# STM32H730_PINOUT.net
KiCad netlist of a schematic drawn in Altium Designer
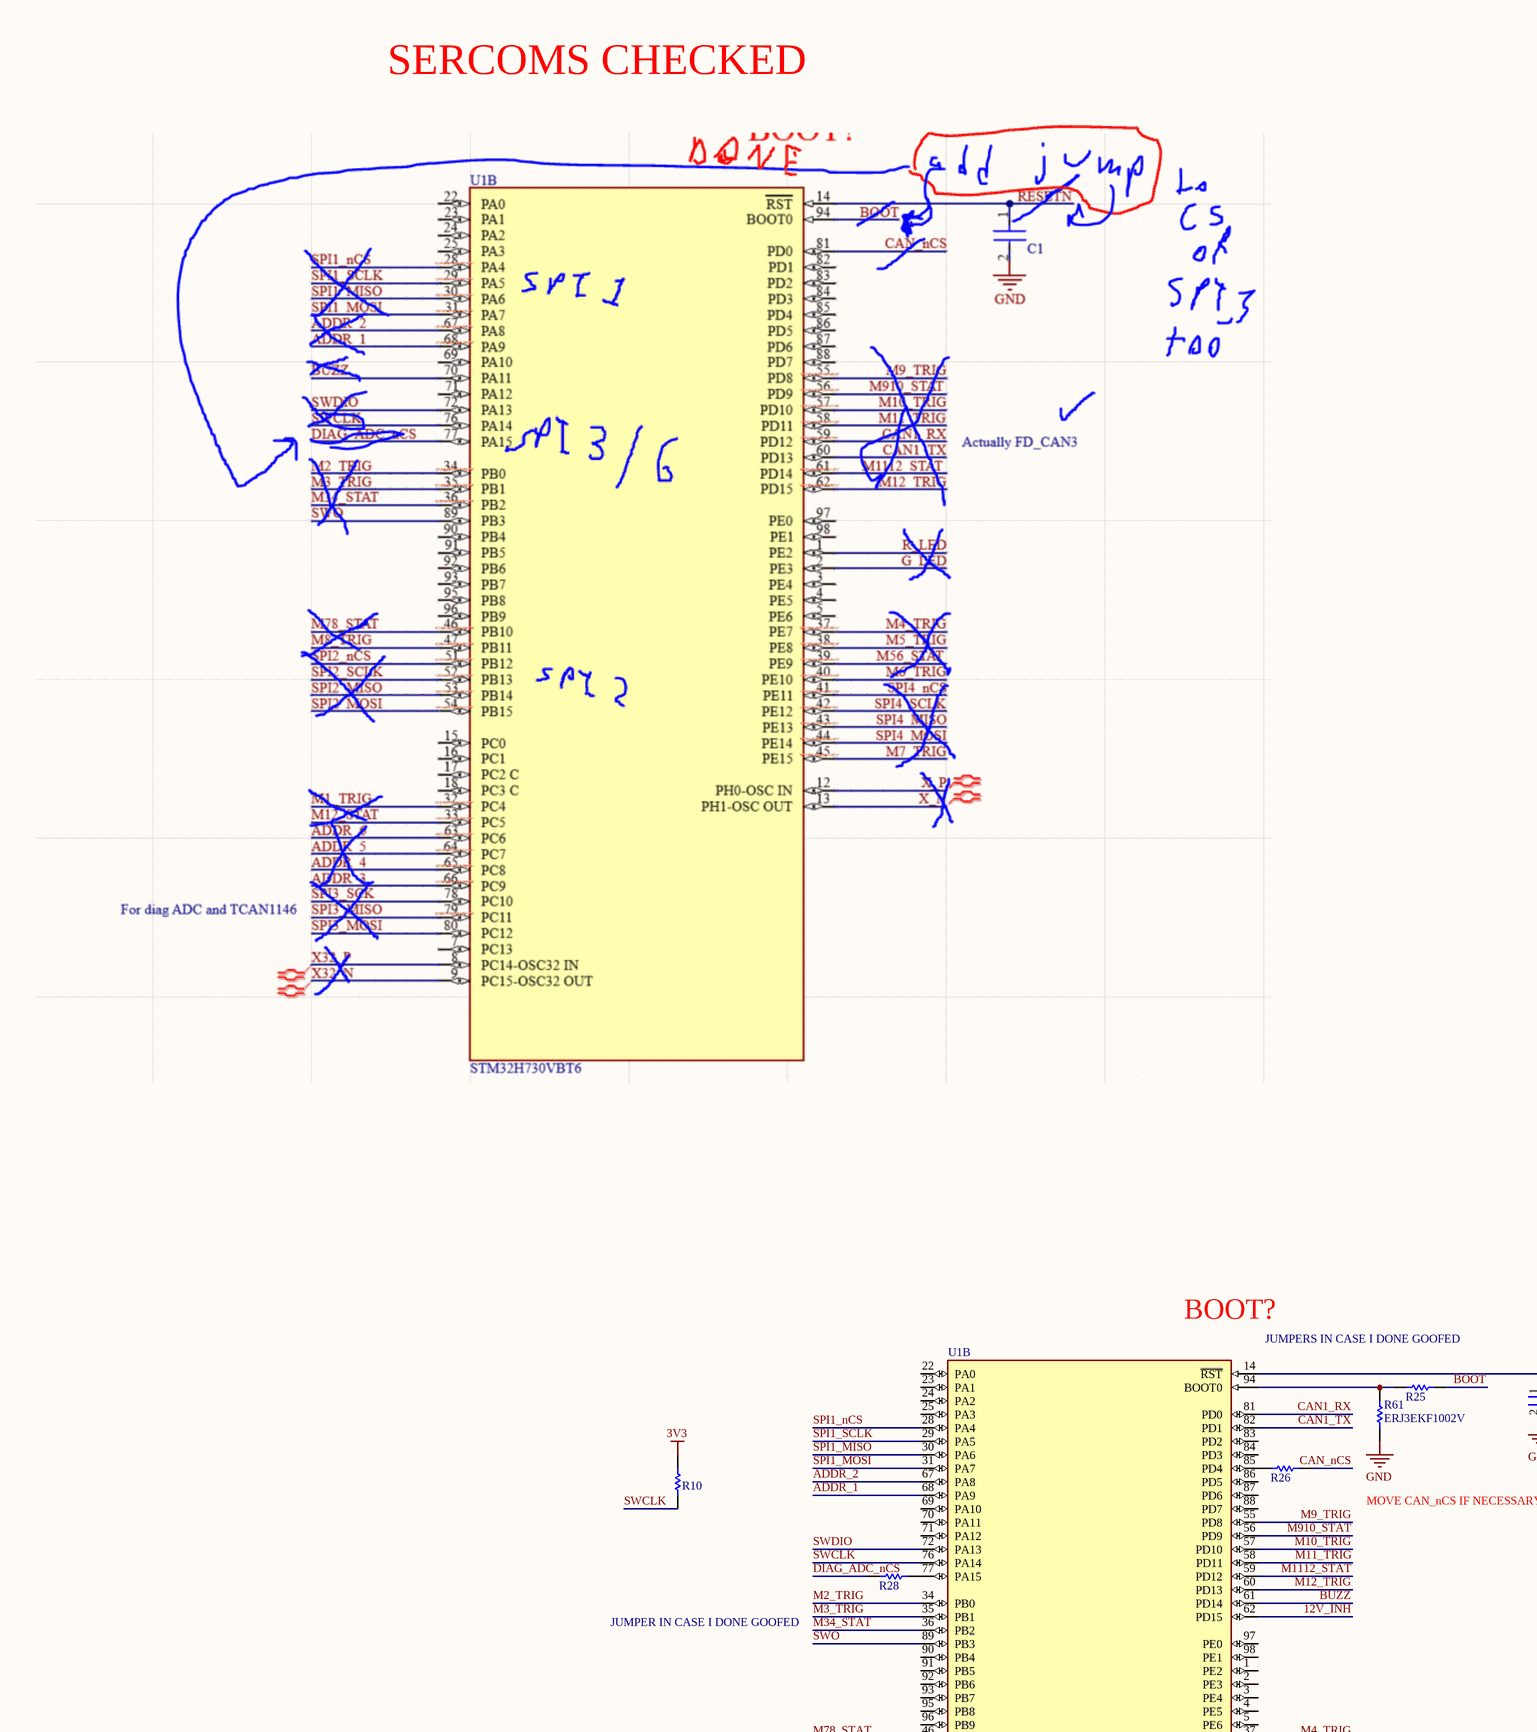
[diagram p0: STM32H730_PINOUT.SchDoc, top left]
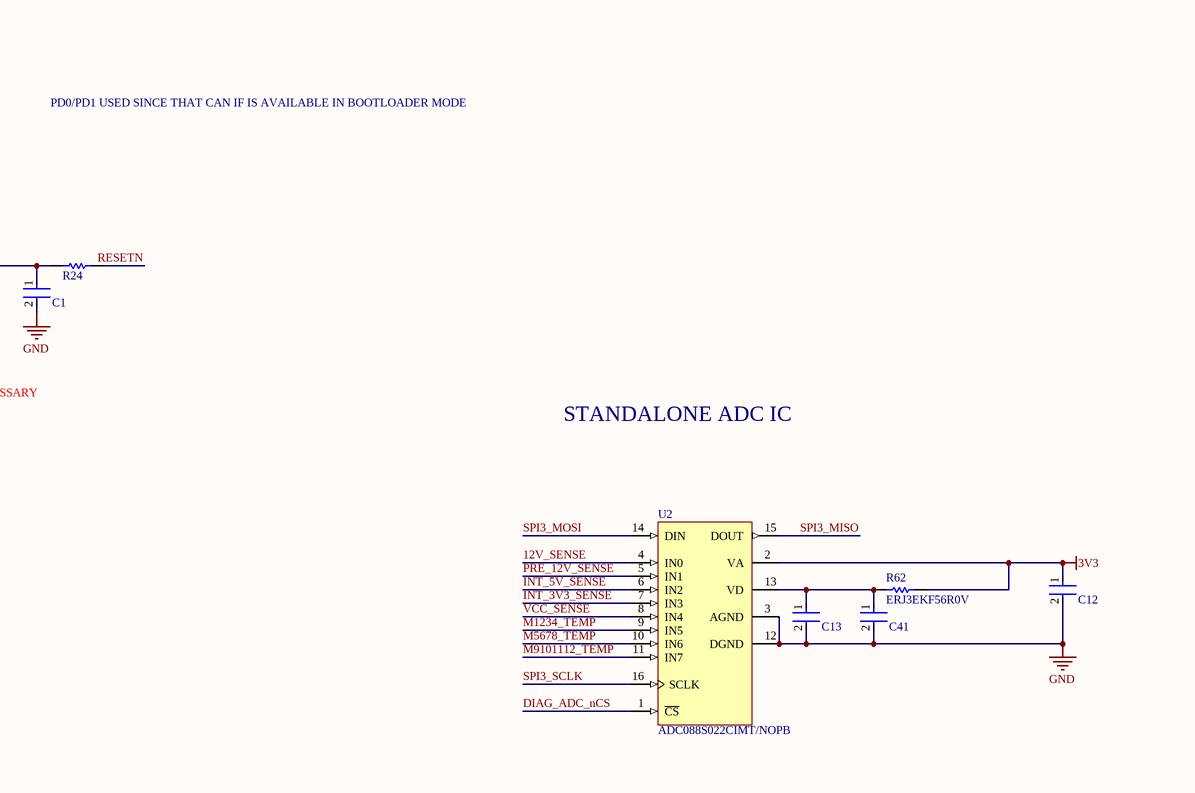
[diagram p1: STM32H730_PINOUT.SchDoc, top middle]
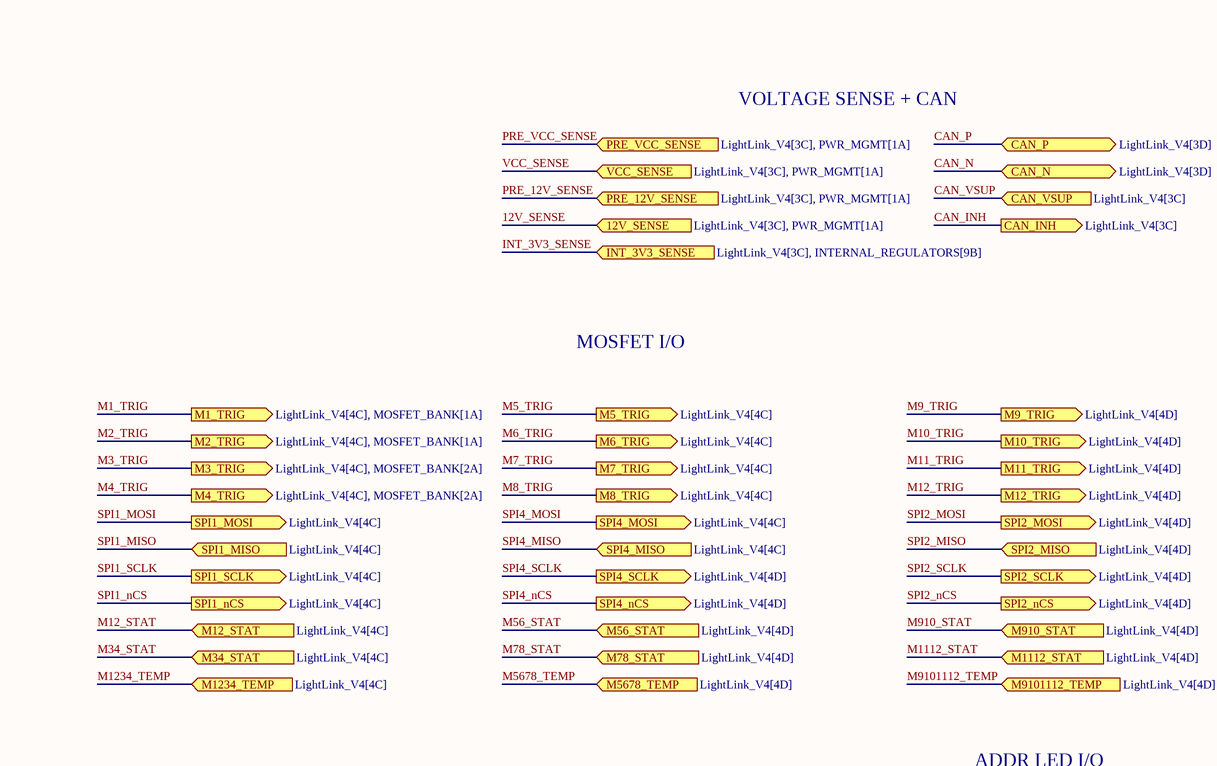
[diagram p2: STM32H730_PINOUT.SchDoc, top right]
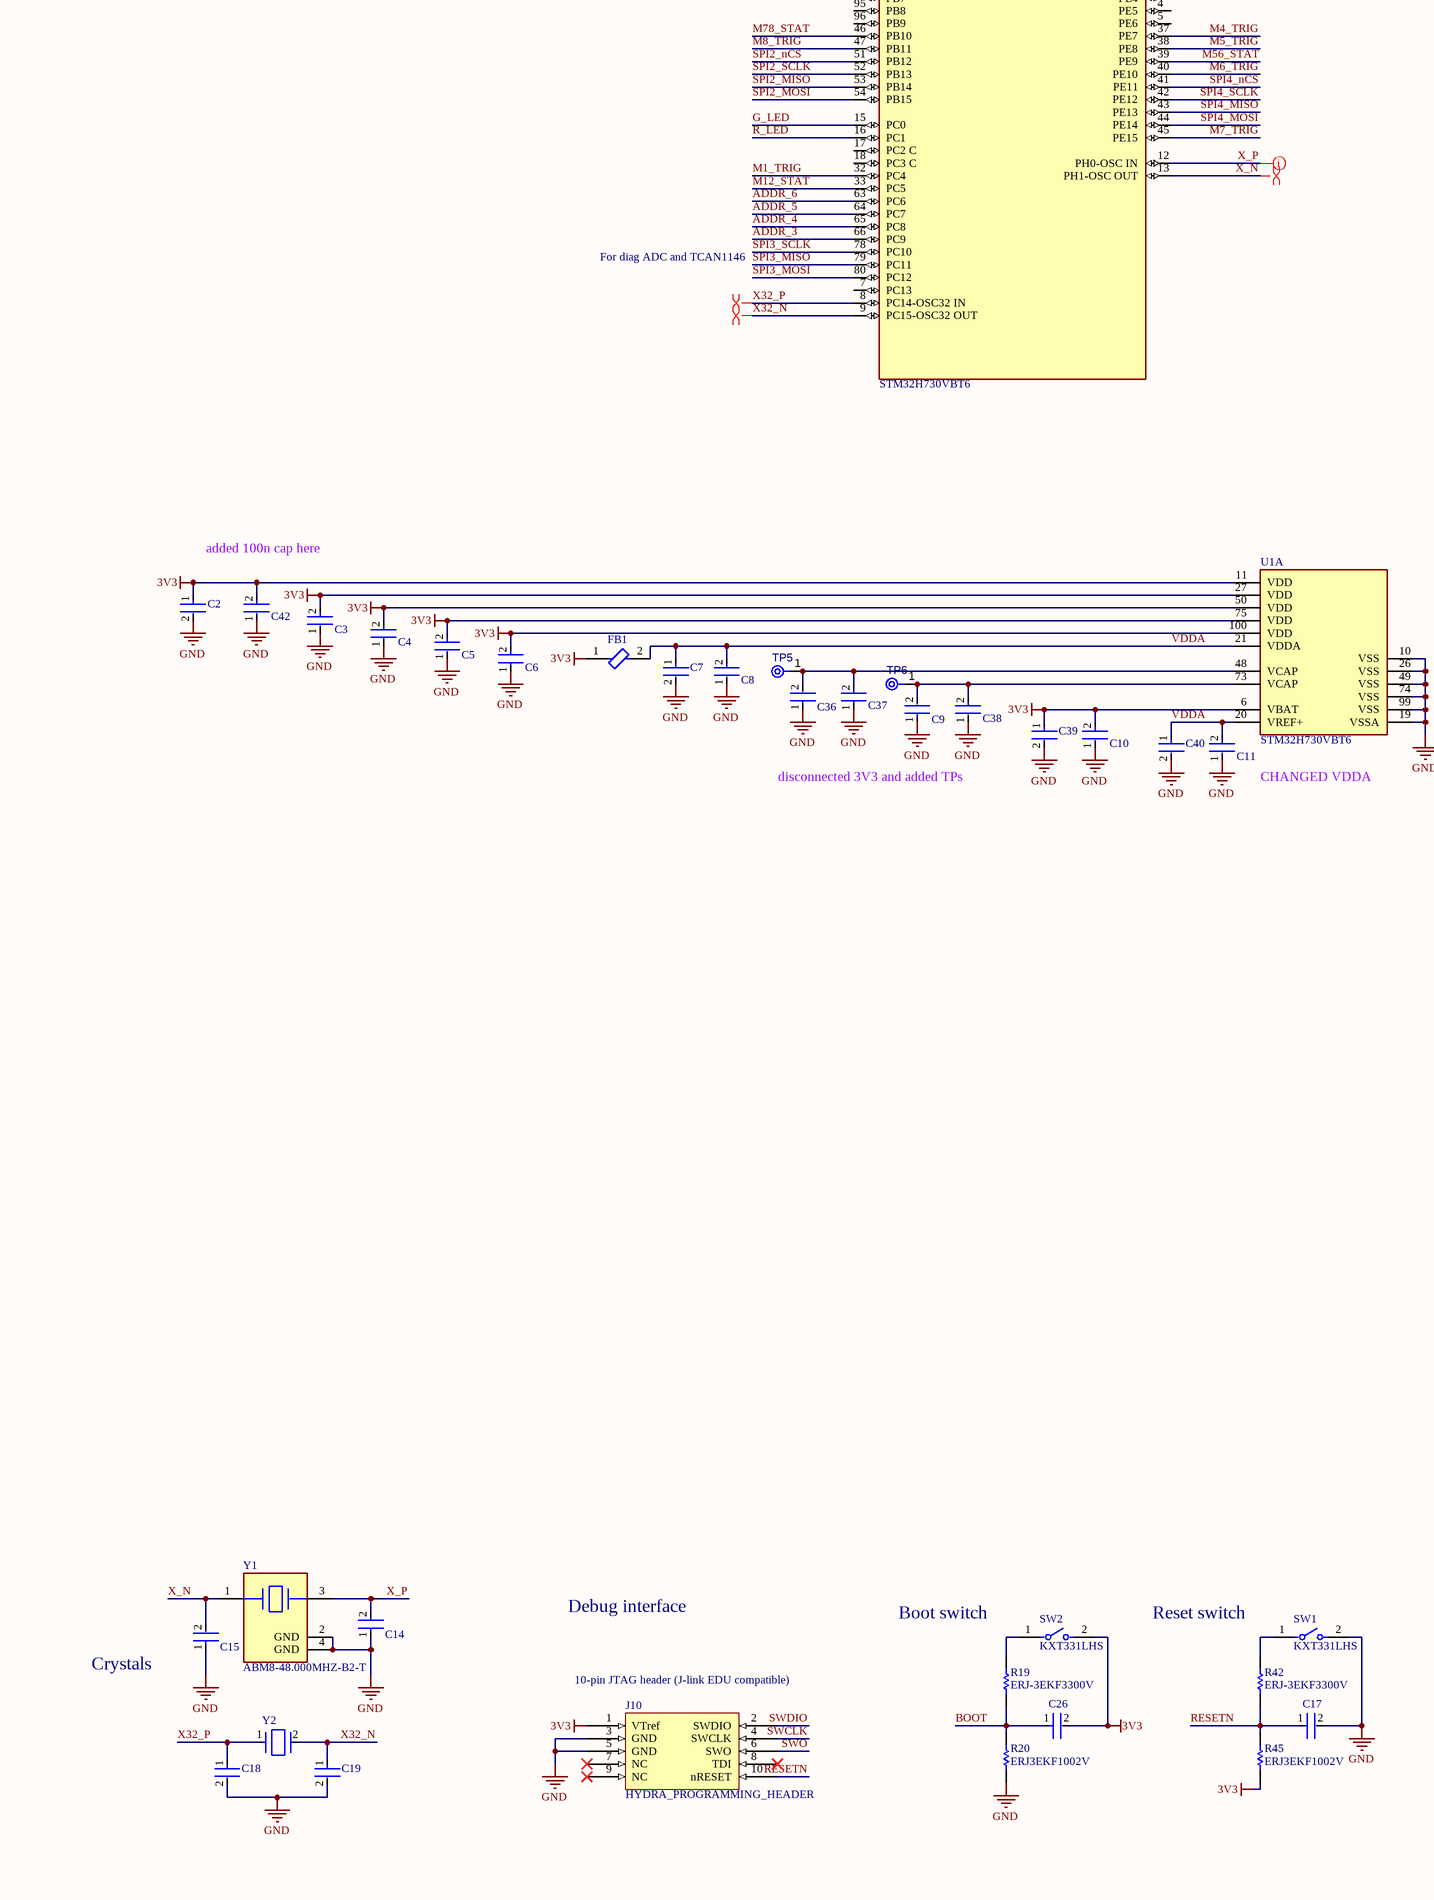
[diagram p3: STM32H730_PINOUT.SchDoc, bottom left]
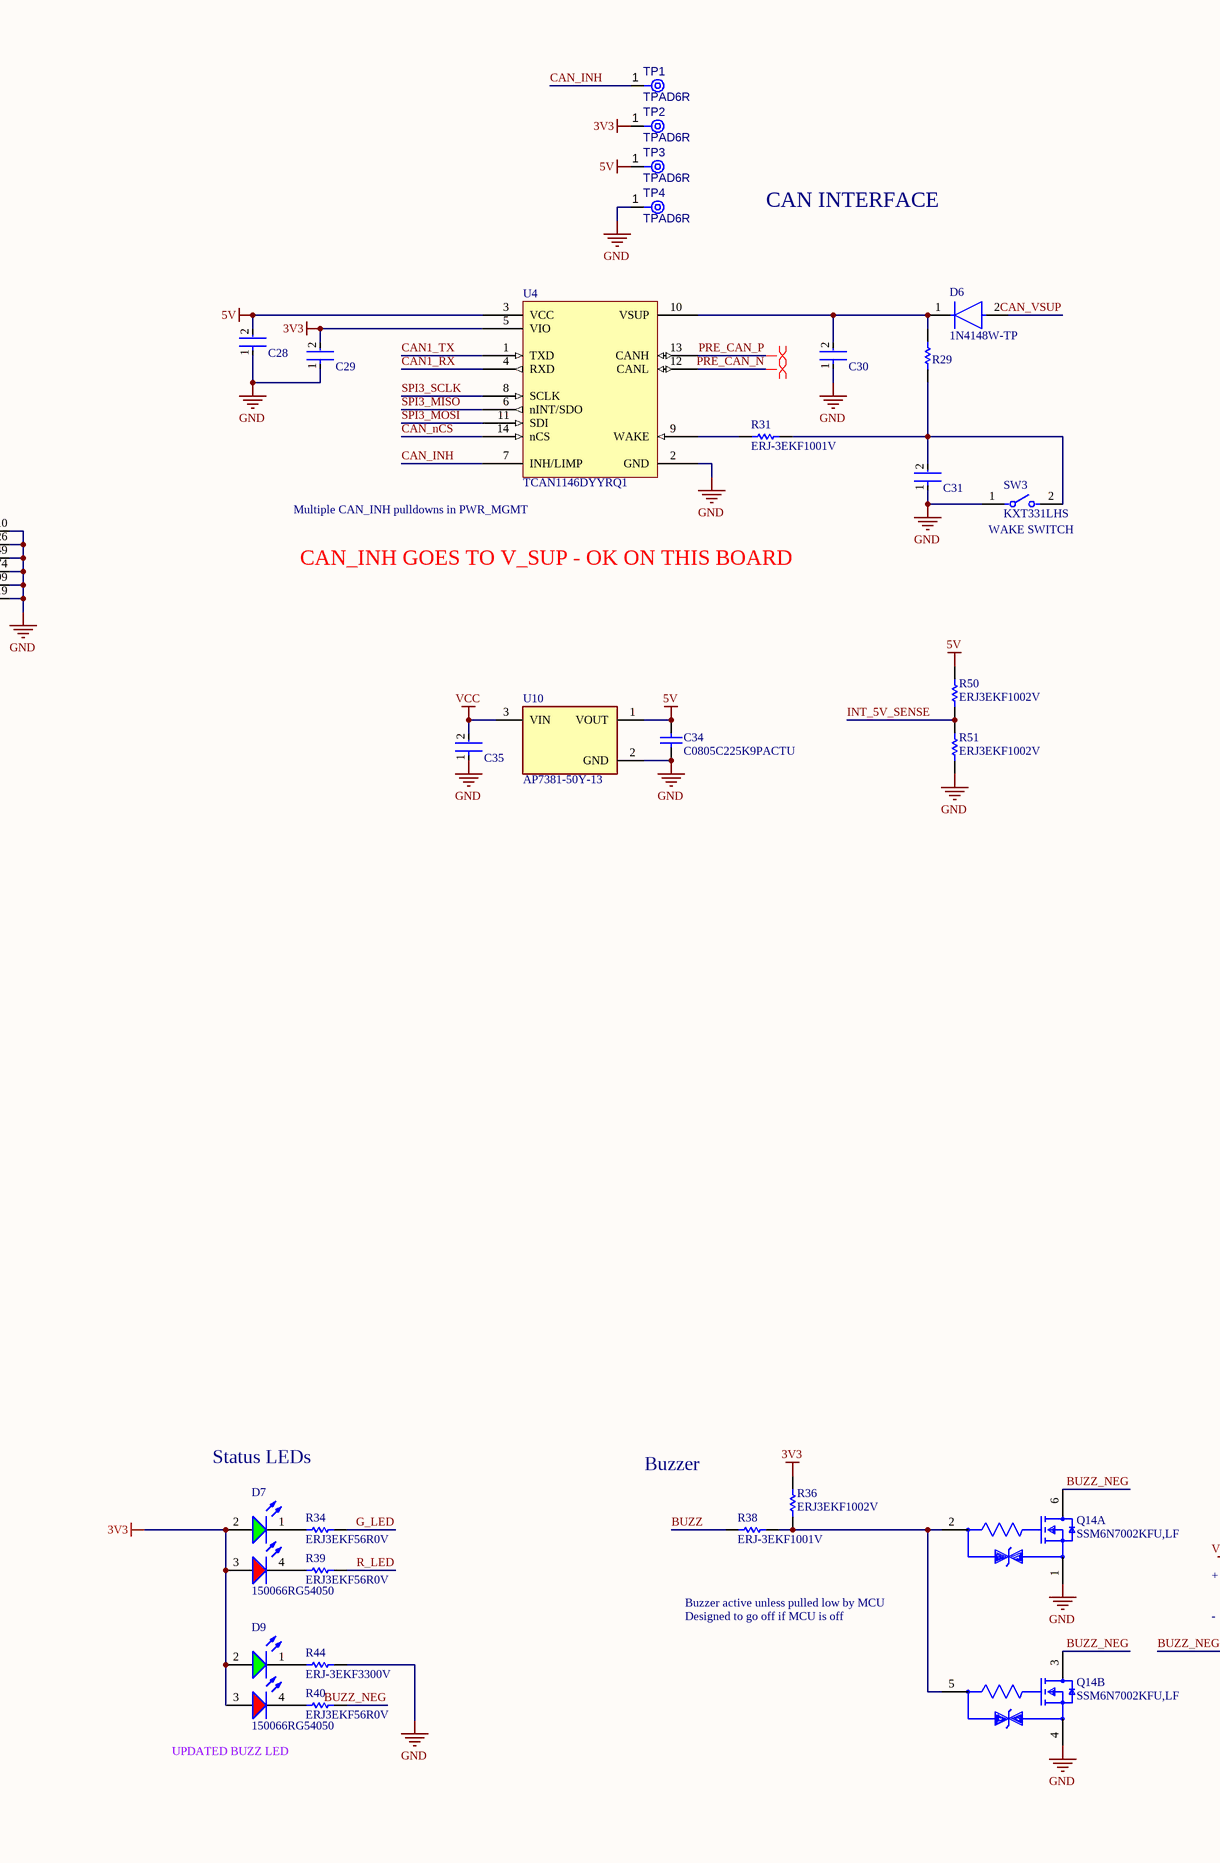
[diagram p4: STM32H730_PINOUT.SchDoc, bottom middle]
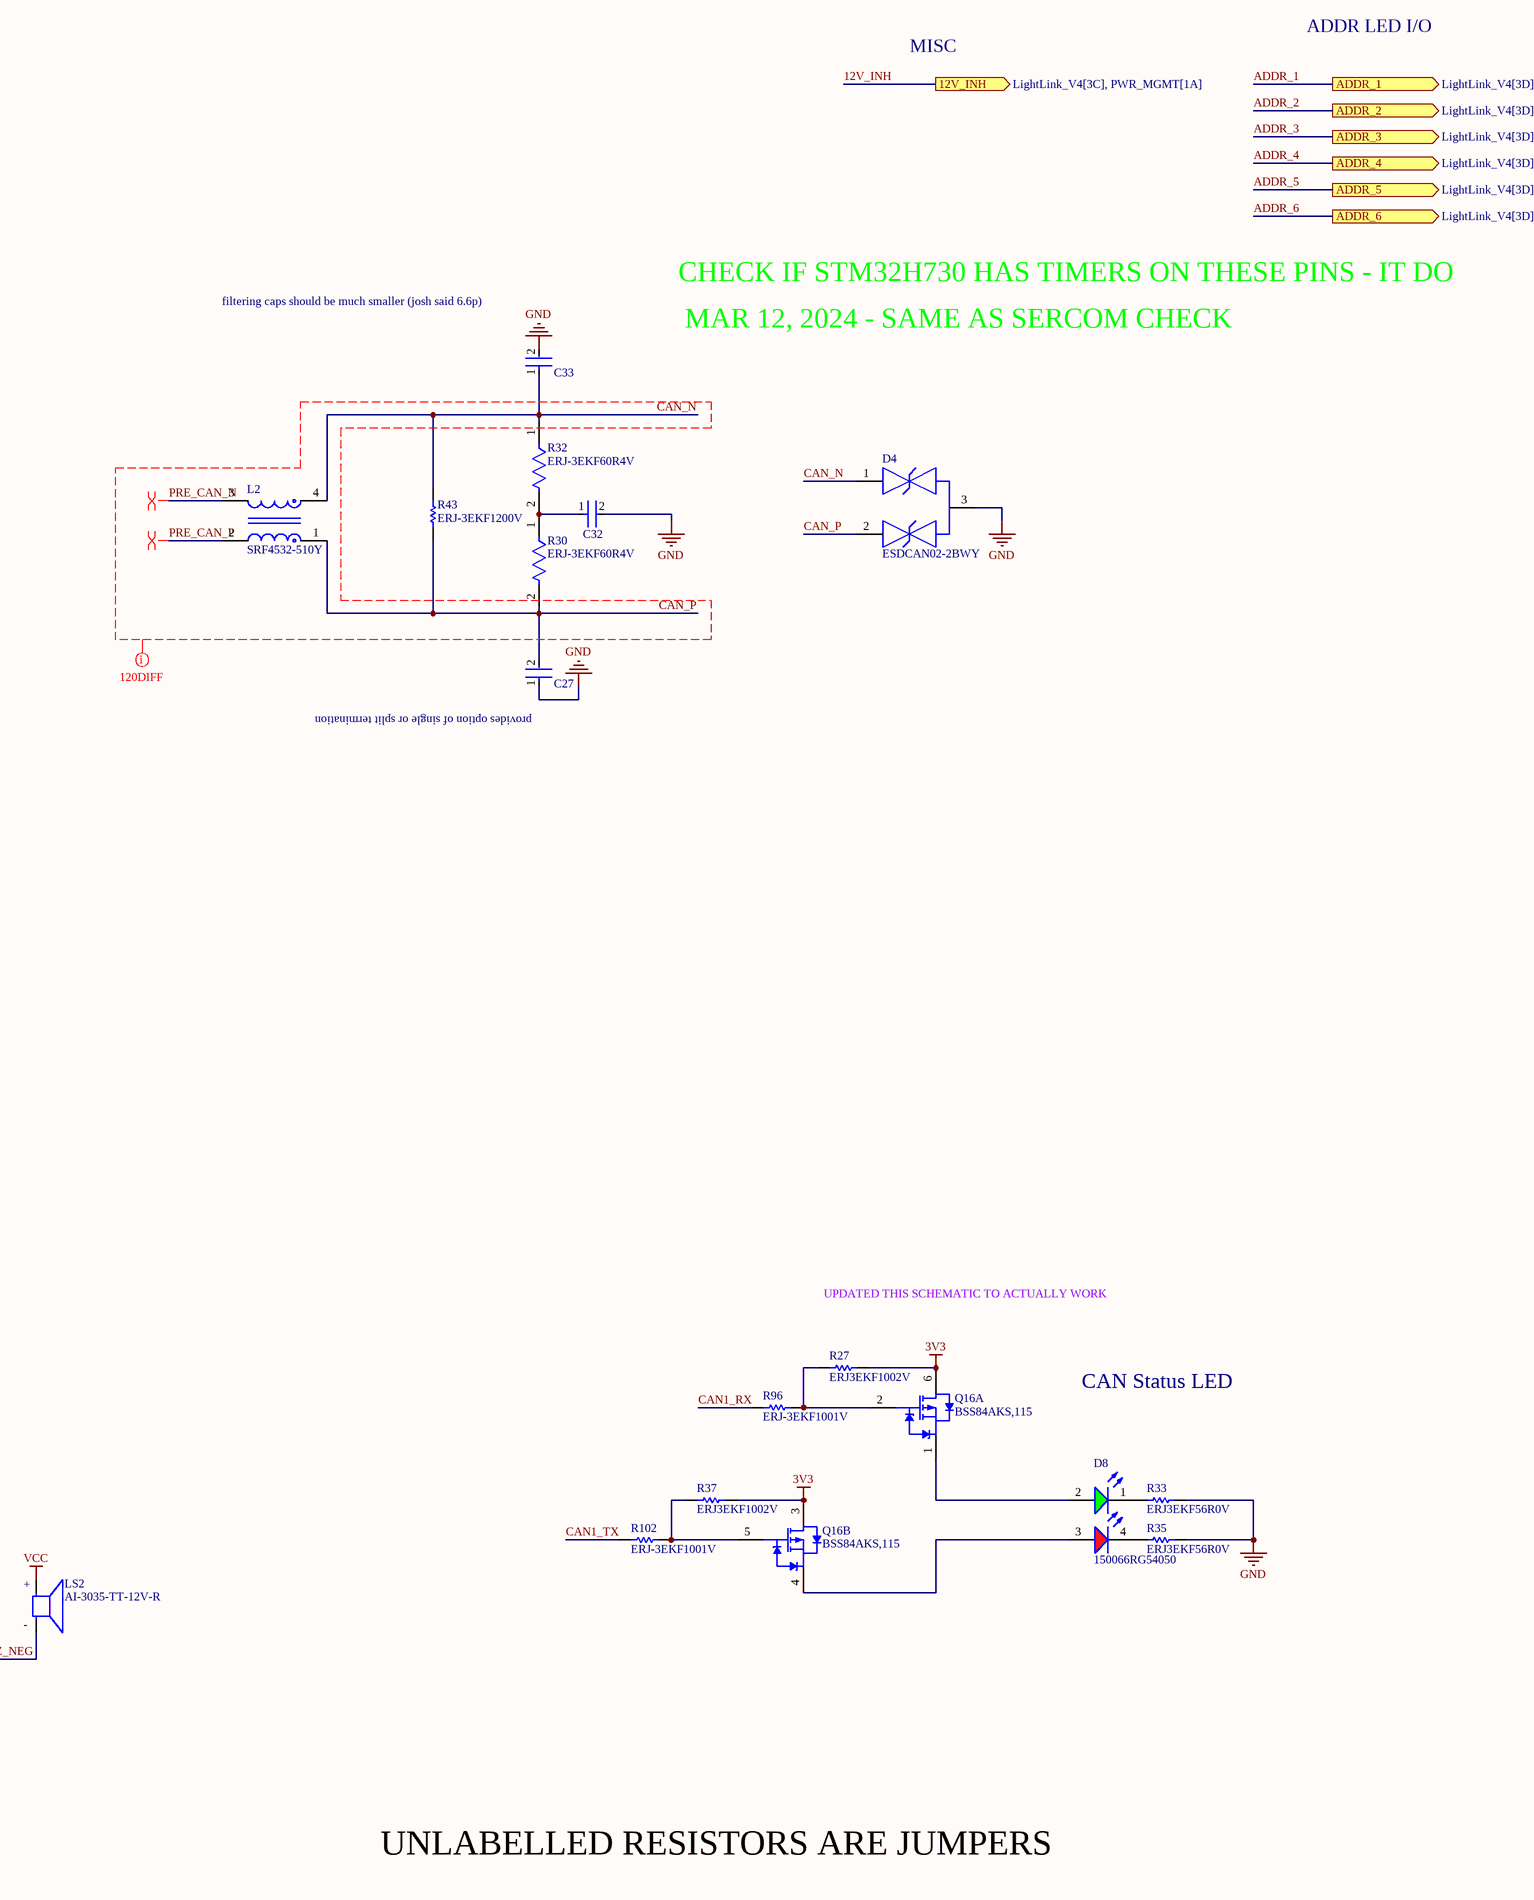
[diagram p5: STM32H730_PINOUT.SchDoc, bottom right]

(export (version "E")
  (design (tool "Eeschema 10.0.6"))
  (components
    (comp (ref "C1")
      (value "C0402C104K8PACTU")
      (footprint "FP-C0402-BB-MFG")
      (description "CAP CER 0.1UF 10V X5R 0402")
      (fields (field (name "MANUFACTURER") "Kemet") (field (name "TOLERANCE") "0.1"))
      (libsource (lib "Altium Content Vault") (part "b4654b650e69147ec39a6b967a45e02"))
    )
    (comp (ref "C2")
      (value "C1005X5R1A475K050BC")
      (footprint "FP-C1005-050-0_15-MFG")
      (description "CAP CER 4.7UF 10V X5R 0402")
      (fields (field (name "TOLERANCE") "10%"))
      (libsource (lib "Altium Content Vault") (part "b4654b650e69147ec39a6b967a45e02"))
    )
    (comp (ref "C3")
      (value "GRM155R71C104KA88D")
      (footprint "FP-GRM15-MFG")
      (description "CAP CER 0.1UF 16V X7R 0402")
      (fields
        (field (name "TOLERANCE") "10%")
        (field (name "OCTOPART") "https://octopart.com/grm155r71c104ka88d-murata-196880")
      )
      (libsource (lib "Altium Content Vault") (part "236180d848d6139a670b325ea6854c9"))
    )
    (comp (ref "C4")
      (value "GRM155R71C104KA88D")
      (footprint "FP-GRM15-MFG")
      (description "CAP CER 0.1UF 16V X7R 0402")
      (fields
        (field (name "TOLERANCE") "10%")
        (field (name "OCTOPART") "https://octopart.com/grm155r71c104ka88d-murata-196880")
      )
      (libsource (lib "Altium Content Vault") (part "236180d848d6139a670b325ea6854c9"))
    )
    (comp (ref "C5")
      (value "GRM155R71C104KA88D")
      (footprint "FP-GRM15-MFG")
      (description "CAP CER 0.1UF 16V X7R 0402")
      (fields
        (field (name "TOLERANCE") "10%")
        (field (name "OCTOPART") "https://octopart.com/grm155r71c104ka88d-murata-196880")
      )
      (libsource (lib "Altium Content Vault") (part "236180d848d6139a670b325ea6854c9"))
    )
    (comp (ref "C6")
      (value "GRM155R71C104KA88D")
      (footprint "FP-GRM15-MFG")
      (description "CAP CER 0.1UF 16V X7R 0402")
      (fields
        (field (name "TOLERANCE") "10%")
        (field (name "OCTOPART") "https://octopart.com/grm155r71c104ka88d-murata-196880")
      )
      (libsource (lib "Altium Content Vault") (part "236180d848d6139a670b325ea6854c9"))
    )
    (comp (ref "C7")
      (value "EMK105BJ105KV-F")
      (footprint "FP-0402-L_1_0_0_05-W_0_5-IPC_A")
      (description "None")
      (fields (field (name "TOLERANCE") "10%"))
      (libsource (lib "Altium Content Vault") (part "b4654b650e69147ec39a6b967a45e02"))
    )
    (comp (ref "C8")
      (value "GRM155R71C104KA88D")
      (footprint "FP-GRM15-MFG")
      (description "CAP CER 0.1UF 16V X7R 0402")
      (fields
        (field (name "TOLERANCE") "10%")
        (field (name "OCTOPART") "https://octopart.com/grm155r71c104ka88d-murata-196880")
      )
      (libsource (lib "Altium Content Vault") (part "236180d848d6139a670b325ea6854c9"))
    )
    (comp (ref "C9")
      (value "C1005X7S1A225K050BC")
      (footprint "FP-C1005-050-0_15-0_1-MFG")
      (description "CAP CER 2.2UF 10V X7S 0402")
      (fields (field (name "TOLERANCE") "10%"))
      (libsource (lib "Altium Content Vault") (part "b4654b650e69147ec39a6b967a45e02"))
    )
    (comp (ref "C10")
      (value "GRM155R71C104KA88D")
      (footprint "FP-GRM15-MFG")
      (description "CAP CER 0.1UF 16V X7R 0402")
      (fields
        (field (name "TOLERANCE") "10%")
        (field (name "OCTOPART") "https://octopart.com/grm155r71c104ka88d-murata-196880")
      )
      (libsource (lib "Altium Content Vault") (part "236180d848d6139a670b325ea6854c9"))
    )
    (comp (ref "C11")
      (value "GRM155R71C104KA88D")
      (footprint "FP-GRM15-MFG")
      (description "CAP CER 0.1UF 16V X7R 0402")
      (fields
        (field (name "TOLERANCE") "10%")
        (field (name "OCTOPART") "https://octopart.com/grm155r71c104ka88d-murata-196880")
      )
      (libsource (lib "Altium Content Vault") (part "236180d848d6139a670b325ea6854c9"))
    )
    (comp (ref "C12")
      (value "C0402C104K8PACTU")
      (footprint "FP-C0402-BB-MFG")
      (description "CAP CER 0.1UF 10V X5R 0402")
      (fields (field (name "MANUFACTURER") "Kemet") (field (name "TOLERANCE") "0.1"))
      (libsource (lib "Altium Content Vault") (part "b4654b650e69147ec39a6b967a45e02"))
    )
    (comp (ref "C13")
      (value "C0402C104K8PACTU")
      (footprint "FP-C0402-BB-MFG")
      (description "CAP CER 0.1UF 10V X5R 0402")
      (fields (field (name "MANUFACTURER") "Kemet") (field (name "TOLERANCE") "0.1"))
      (libsource (lib "Altium Content Vault") (part "b4654b650e69147ec39a6b967a45e02"))
    )
    (comp (ref "C14")
      (value "08051A6R8CAT2A")
      (footprint "FP-0805-L_2_01_0_2-W_1_25-MFG")
      (description "General Purpose Ceramic Capacitor, 0805, 6.8pF, 0.25pF, C0G, 30ppm/°C, 100V")
      (fields (field (name "VOLTAGE") "100V") (field (name "TOLERANCE") "5%"))
      (libsource (lib "Altium Content Vault") (part "02cd4be3c70576c341d710602a673aa"))
    )
    (comp (ref "C15")
      (value "08051A6R8CAT2A")
      (footprint "FP-0805-L_2_01_0_2-W_1_25-MFG")
      (description "General Purpose Ceramic Capacitor, 0805, 6.8pF, 0.25pF, C0G, 30ppm/°C, 100V")
      (fields (field (name "VOLTAGE") "100V") (field (name "TOLERANCE") "5%"))
      (libsource (lib "Altium Content Vault") (part "02cd4be3c70576c341d710602a673aa"))
    )
    (comp (ref "C17")
      (value "C0402C104K8PACTU")
      (footprint "FP-C0402-BB-MFG")
      (description "CAP CER 0.1UF 10V X5R 0402")
      (fields (field (name "MANUFACTURER") "Kemet") (field (name "TOLERANCE") "0.1"))
      (libsource (lib "Altium Content Vault") (part "b4654b650e69147ec39a6b967a45e02"))
    )
    (comp (ref "C18")
      (value "C0805C180J5GACTU")
      (footprint "FP-C0805C-DN-MFG")
      (description "CAP CER 18PF 50V C0G/NP0 0805")
      (fields
        (field (name "OCTOPART") "https://octopart.com/c0805c180j5gactu-kemet-144810")
        (field (name "TOLERANCE") "0.05")
      )
      (libsource (lib "Altium Content Vault") (part "b4654b650e69147ec39a6b967a45e02"))
    )
    (comp (ref "C19")
      (value "C0805C180J5GACTU")
      (footprint "FP-C0805C-DN-MFG")
      (description "CAP CER 18PF 50V C0G/NP0 0805")
      (fields
        (field (name "OCTOPART") "https://octopart.com/c0805c180j5gactu-kemet-144810")
        (field (name "TOLERANCE") "0.05")
      )
      (libsource (lib "Altium Content Vault") (part "b4654b650e69147ec39a6b967a45e02"))
    )
    (comp (ref "C26")
      (value "C0402C104K8PACTU")
      (footprint "FP-C0402-BB-MFG")
      (description "CAP CER 0.1UF 10V X5R 0402")
      (fields (field (name "MANUFACTURER") "Kemet") (field (name "TOLERANCE") "0.1"))
      (libsource (lib "Altium Content Vault") (part "b4654b650e69147ec39a6b967a45e02"))
    )
    (comp (ref "C27")
      (value "C0402C104K8PACTU")
      (footprint "FP-C0402-BB-MFG")
      (description "CAP CER 0.1UF 10V X5R 0402")
      (fields (field (name "MANUFACTURER") "Kemet") (field (name "TOLERANCE") "0.1"))
      (libsource (lib "Altium Content Vault") (part "b4654b650e69147ec39a6b967a45e02"))
    )
    (comp (ref "C28")
      (value "C0402C104K8PACTU")
      (footprint "FP-C0402-BB-MFG")
      (description "CAP CER 0.1UF 10V X5R 0402")
      (fields (field (name "MANUFACTURER") "Kemet") (field (name "TOLERANCE") "0.1"))
      (libsource (lib "Altium Content Vault") (part "b4654b650e69147ec39a6b967a45e02"))
    )
    (comp (ref "C29")
      (value "C0402C104K8PACTU")
      (footprint "FP-C0402-BB-MFG")
      (description "CAP CER 0.1UF 10V X5R 0402")
      (fields (field (name "MANUFACTURER") "Kemet") (field (name "TOLERANCE") "0.1"))
      (libsource (lib "Altium Content Vault") (part "b4654b650e69147ec39a6b967a45e02"))
    )
    (comp (ref "C30")
      (value "C0402C104K8PACTU")
      (footprint "FP-C0402-BB-MFG")
      (description "CAP CER 0.1UF 10V X5R 0402")
      (fields (field (name "MANUFACTURER") "Kemet") (field (name "TOLERANCE") "0.1"))
      (libsource (lib "Altium Content Vault") (part "b4654b650e69147ec39a6b967a45e02"))
    )
    (comp (ref "C31")
      (value "C0402C104K8PACTU")
      (footprint "FP-C0402-BB-MFG")
      (description "CAP CER 0.1UF 10V X5R 0402")
      (fields (field (name "MANUFACTURER") "Kemet") (field (name "TOLERANCE") "0.1"))
      (libsource (lib "Altium Content Vault") (part "b4654b650e69147ec39a6b967a45e02"))
    )
    (comp (ref "C32")
      (value "C0402C104K8PACTU")
      (footprint "FP-C0402-BB-MFG")
      (description "CAP CER 0.1UF 10V X5R 0402")
      (fields (field (name "MANUFACTURER") "Kemet") (field (name "TOLERANCE") "0.1"))
      (libsource (lib "Altium Content Vault") (part "b4654b650e69147ec39a6b967a45e02"))
    )
    (comp (ref "C33")
      (value "C0402C104K8PACTU")
      (footprint "FP-C0402-BB-MFG")
      (description "CAP CER 0.1UF 10V X5R 0402")
      (fields (field (name "MANUFACTURER") "Kemet") (field (name "TOLERANCE") "0.1"))
      (libsource (lib "Altium Content Vault") (part "b4654b650e69147ec39a6b967a45e02"))
    )
    (comp (ref "C34")
      (value "C0805C225K9PACTU")
      (footprint "CAPC2013X145X50ML20T25")
      (fields (field (name "MANUFACTURER") "Kemet"))
      (libsource (lib "Altium Content Vault") (part "CAP"))
    )
    (comp (ref "C35")
      (value "C0402C104K8PACTU")
      (footprint "FP-C0402-BB-MFG")
      (description "CAP CER 0.1UF 10V X5R 0402")
      (fields (field (name "MANUFACTURER") "Kemet") (field (name "TOLERANCE") "0.1"))
      (libsource (lib "Altium Content Vault") (part "b4654b650e69147ec39a6b967a45e02"))
    )
    (comp (ref "C36")
      (value "C1005X7S1A225K050BC")
      (footprint "FP-C1005-050-0_15-0_1-MFG")
      (description "CAP CER 2.2UF 10V X7S 0402")
      (fields (field (name "TOLERANCE") "10%"))
      (libsource (lib "Altium Content Vault") (part "b4654b650e69147ec39a6b967a45e02"))
    )
    (comp (ref "C37")
      (value "GRM155R71C104KA88D")
      (footprint "FP-GRM15-MFG")
      (description "CAP CER 0.1UF 16V X7R 0402")
      (fields
        (field (name "TOLERANCE") "10%")
        (field (name "OCTOPART") "https://octopart.com/grm155r71c104ka88d-murata-196880")
      )
      (libsource (lib "Altium Content Vault") (part "236180d848d6139a670b325ea6854c9"))
    )
    (comp (ref "C38")
      (value "GRM155R71C104KA88D")
      (footprint "FP-GRM15-MFG")
      (description "CAP CER 0.1UF 16V X7R 0402")
      (fields
        (field (name "TOLERANCE") "10%")
        (field (name "OCTOPART") "https://octopart.com/grm155r71c104ka88d-murata-196880")
      )
      (libsource (lib "Altium Content Vault") (part "236180d848d6139a670b325ea6854c9"))
    )
    (comp (ref "C39")
      (value "EMK105BJ105KV-F")
      (footprint "FP-0402-L_1_0_0_05-W_0_5-IPC_A")
      (description "None")
      (fields (field (name "TOLERANCE") "10%"))
      (libsource (lib "Altium Content Vault") (part "b4654b650e69147ec39a6b967a45e02"))
    )
    (comp (ref "C40")
      (value "EMK105BJ105KV-F")
      (footprint "FP-0402-L_1_0_0_05-W_0_5-IPC_A")
      (description "None")
      (fields (field (name "TOLERANCE") "10%"))
      (libsource (lib "Altium Content Vault") (part "b4654b650e69147ec39a6b967a45e02"))
    )
    (comp (ref "C41")
      (value "C0402C104K8PACTU")
      (footprint "FP-C0402-BB-MFG")
      (description "CAP CER 0.1UF 10V X5R 0402")
      (fields (field (name "MANUFACTURER") "Kemet") (field (name "TOLERANCE") "0.1"))
      (libsource (lib "Altium Content Vault") (part "b4654b650e69147ec39a6b967a45e02"))
    )
    (comp (ref "C42")
      (value "GRM155R71C104KA88D")
      (footprint "FP-GRM15-MFG")
      (description "CAP CER 0.1UF 16V X7R 0402")
      (fields
        (field (name "TOLERANCE") "10%")
        (field (name "OCTOPART") "https://octopart.com/grm155r71c104ka88d-murata-196880")
      )
      (libsource (lib "Altium Content Vault") (part "236180d848d6139a670b325ea6854c9"))
    )
    (comp (ref "D4")
      (value "ESDCAN02-2BWY")
      (footprint "FP-SOT323-3L-MFG")
      (description "TVS DIODE 26.5V 44V SOT323-3")
      (fields
        (field (name "MANUFACTURER") "STMicroelectronics")
        (field (name "OCTOPART") "https://octopart.com/esdcan02-2bwy-stmicroelectronics-58631133")
      )
      (libsource (lib "Altium Content Vault") (part "0b9019fb5e52ed66df21ec1535be59d"))
    )
    (comp (ref "D6")
      (value "1N4148W-TP")
      (footprint "FP-SOD-123-IPC_A")
      (description "DIODE GEN PURP 100V 150MA SOD123")
      (libsource (lib "Altium Content Vault") (part "d7152d700b627762746794eb795d46e"))
    )
    (comp (ref "D7")
      (value "150066RG54050")
      (footprint "WL-SBCD_0606")
      (description "Led, Red/Grn, 180Mcd/230Mcd, 624Nm/525Nm Rohs Compliant: Yes")
      (libsource (lib "uORocketry Hardware") (part "WL-SBCD_0606_Red & Green"))
    )
    (comp (ref "D8")
      (value "150066RG54050")
      (footprint "WL-SBCD_0606")
      (description "Led, Red/Grn, 180Mcd/230Mcd, 624Nm/525Nm Rohs Compliant: Yes")
      (libsource (lib "uORocketry Hardware") (part "WL-SBCD_0606_Red & Green"))
    )
    (comp (ref "D9")
      (value "150066RG54050")
      (footprint "WL-SBCD_0606")
      (description "Led, Red/Grn, 180Mcd/230Mcd, 624Nm/525Nm Rohs Compliant: Yes")
      (libsource (lib "uORocketry Hardware") (part "WL-SBCD_0606_Red & Green"))
    )
    (comp (ref "FB1")
      (value "BLM15PX601SN1D")
      (footprint "FP-BLM15-0_05-MFG")
      (description "Chip Ferrite Bead, 0402, 600Ω @ 100MHz, 0.23Ω, 25%, 900mA")
      (fields (field (name "TOLERANCE") "25%"))
      (libsource (lib "Altium Content Vault") (part "5f30dd21d616792df468990f7003faa"))
    )
    (comp (ref "J10")
      (value "HYDRA_PROGRAMMING_HEADER")
      (footprint "3220-10-0300-00-Footprint-1")
      (description "CONN HEADER SMD 10POS 1.27MM (specifically compatible with J-Link EDU cable) PN: 3220-10-0300-00")
      (libsource (lib "uORocketry Hardware") (part "3220-10-0300-00-Symbol-1"))
    )
    (comp (ref "L2")
      (value "SRF4532-510Y")
      (footprint "FP-SRF4532-MFG")
      (description "CMC 51UH 200MA 2LN 2KOHM SMD")
      (fields (field (name "TOLERANCE") "50%"))
      (libsource (lib "Altium Content Vault") (part "aca3f6a10b859f211cca95010157f3b"))
    )
    (comp (ref "LS2")
      (value "AI-3035-TT-12V-R")
      (footprint "AI-3035-TT-12V-R-Footprint-1")
      (description "Audio Indicator 12V 12mA 110dBA 3.5KHz Resonant Frequency Thru-Hole")
      (libsource (lib "uORocketry Hardware") (part "AI-3035-TT-12V-R"))
    )
    (comp (ref "Q14")
      (value "SSM6N7002KFU,LF")
      (footprint "FP-SSOP6-P-0_65A-MFG")
      (description "MOSFET 2N-CH 60V 0.3A")
      (libsource (lib "Altium Content Vault") (part "088aa6ac103fdeebe0d1c52ece6b7b9"))
    )
    (comp (ref "Q16")
      (value "BSS84AKS,115")
      (footprint "NXP-SOT363_L")
      (description "Dual P-Channel Trench MOSFET, -50 V, -0.16 A, -55 to 150 degC, 6-Pin SOT363, Tape and Reel")
      (fields (field (name "MANUFACTURER") "NXP Semiconductors"))
      (libsource (lib "Altium Content Vault") (part "NXP-PPMOS-SGDSGD-6_A"))
    )
    (comp (ref "R10")
      (value "ERJ3EKF1002V")
      (footprint "RESC1609X55X30LL15T15")
      (description "Chip Resistor, 10 KOhm, +/- 1%, 0.1 W, -55 to 155 degC, 0603 (1608 Metric), RoHS, Tape and Reel")
      (fields (field (name "TOLERANCE") "1%") (field (name "MANUFACTURER") "Panasonic"))
      (libsource (lib "Altium Content Vault") (part "RES-2"))
    )
    (comp (ref "R19")
      (value "ERJ-3EKF3300V")
      (footprint "RESC1608X55X30LL15T15")
      (description "Chip Resistor, 330 Ohm, +/- 1%, 0.1 W, -55 to 155 degC, 0603 (1608 Metric), RoHS, Tape and Reel")
      (libsource (lib "Altium Content Vault") (part "RES-2"))
    )
    (comp (ref "R20")
      (value "ERJ3EKF1002V")
      (footprint "RESC1609X55X30LL15T15")
      (description "Chip Resistor, 10 KOhm, +/- 1%, 0.1 W, -55 to 155 degC, 0603 (1608 Metric), RoHS, Tape and Reel")
      (fields (field (name "TOLERANCE") "1%") (field (name "MANUFACTURER") "Panasonic"))
      (libsource (lib "Altium Content Vault") (part "RES-2"))
    )
    (comp (ref "R24")
      (value "0402 JUMPER 0 OHM")
      (footprint "RESC1005X40X25NL05T05")
      (description "READ THE NAME")
      (libsource (lib "uORocketry Hardware") (part "RES"))
    )
    (comp (ref "R25")
      (value "0402 JUMPER 0 OHM")
      (footprint "RESC1005X40X25NL05T05")
      (description "READ THE NAME")
      (libsource (lib "uORocketry Hardware") (part "RES"))
    )
    (comp (ref "R26")
      (value "0402 JUMPER 0 OHM")
      (footprint "RESC1005X40X25NL05T05")
      (description "READ THE NAME")
      (libsource (lib "uORocketry Hardware") (part "RES"))
    )
    (comp (ref "R27")
      (value "ERJ3EKF1002V")
      (footprint "RESC1609X55X30LL15T15")
      (description "Chip Resistor, 10 KOhm, +/- 1%, 0.1 W, -55 to 155 degC, 0603 (1608 Metric), RoHS, Tape and Reel")
      (fields (field (name "TOLERANCE") "1%") (field (name "MANUFACTURER") "Panasonic"))
      (libsource (lib "Altium Content Vault") (part "RES-2"))
    )
    (comp (ref "R28")
      (value "0402 JUMPER 0 OHM")
      (footprint "RESC1005X40X25NL05T05")
      (description "READ THE NAME")
      (libsource (lib "uORocketry Hardware") (part "RES"))
    )
    (comp (ref "R29")
      (value "ERJ3EKF1002V")
      (footprint "RESC1609X55X30LL15T15")
      (description "Chip Resistor, 10 KOhm, +/- 1%, 0.1 W, -55 to 155 degC, 0603 (1608 Metric), RoHS, Tape and Reel")
      (fields (field (name "TOLERANCE") "1%") (field (name "MANUFACTURER") "Panasonic"))
      (libsource (lib "Altium Content Vault") (part "RES-2"))
    )
    (comp (ref "R30")
      (value "ERJ-3EKF60R4V")
      (footprint "FP-ERJ3EK-IPC_C")
      (description "RES SMD 60.4 OHM 1% 1/10W 0603")
      (fields (field (name "TOLERANCE") "1%"))
      (libsource (lib "Altium Content Vault") (part "1029c3af85768c4190bb7ad29bc67b5"))
    )
    (comp (ref "R31")
      (value "ERJ-3EKF1001V")
      (footprint "RESC1608X55X30LL15T15")
      (fields (field (name "MANUFACTURER") "Panasonic"))
      (libsource (lib "Altium Content Vault") (part "RES"))
    )
    (comp (ref "R32")
      (value "ERJ-3EKF60R4V")
      (footprint "FP-ERJ3EK-IPC_C")
      (description "RES SMD 60.4 OHM 1% 1/10W 0603")
      (fields (field (name "TOLERANCE") "1%"))
      (libsource (lib "Altium Content Vault") (part "1029c3af85768c4190bb7ad29bc67b5"))
    )
    (comp (ref "R33")
      (value "ERJ3EKF56R0V")
      (footprint "RESC1608X55X30NL15T15")
      (fields (field (name "MANUFACTURER") "Panasonic"))
      (libsource (lib "Altium Content Vault") (part "RES"))
    )
    (comp (ref "R34")
      (value "ERJ3EKF56R0V")
      (footprint "RESC1608X55X30NL15T15")
      (fields (field (name "MANUFACTURER") "Panasonic"))
      (libsource (lib "Altium Content Vault") (part "RES"))
    )
    (comp (ref "R35")
      (value "ERJ3EKF56R0V")
      (footprint "RESC1608X55X30NL15T15")
      (fields (field (name "MANUFACTURER") "Panasonic"))
      (libsource (lib "Altium Content Vault") (part "RES"))
    )
    (comp (ref "R36")
      (value "ERJ3EKF1002V")
      (footprint "RESC1609X55X30LL15T15")
      (description "Chip Resistor, 10 KOhm, +/- 1%, 0.1 W, -55 to 155 degC, 0603 (1608 Metric), RoHS, Tape and Reel")
      (fields (field (name "TOLERANCE") "1%") (field (name "MANUFACTURER") "Panasonic"))
      (libsource (lib "Altium Content Vault") (part "RES-2"))
    )
    (comp (ref "R37")
      (value "ERJ3EKF1002V")
      (footprint "RESC1609X55X30LL15T15")
      (description "Chip Resistor, 10 KOhm, +/- 1%, 0.1 W, -55 to 155 degC, 0603 (1608 Metric), RoHS, Tape and Reel")
      (fields (field (name "TOLERANCE") "1%") (field (name "MANUFACTURER") "Panasonic"))
      (libsource (lib "Altium Content Vault") (part "RES-2"))
    )
    (comp (ref "R38")
      (value "ERJ-3EKF1001V")
      (footprint "RESC1608X55X30LL15T15")
      (fields (field (name "MANUFACTURER") "Panasonic"))
      (libsource (lib "Altium Content Vault") (part "RES"))
    )
    (comp (ref "R39")
      (value "ERJ3EKF56R0V")
      (footprint "RESC1608X55X30NL15T15")
      (fields (field (name "MANUFACTURER") "Panasonic"))
      (libsource (lib "Altium Content Vault") (part "RES"))
    )
    (comp (ref "R40")
      (value "ERJ3EKF56R0V")
      (footprint "RESC1608X55X30NL15T15")
      (fields (field (name "MANUFACTURER") "Panasonic"))
      (libsource (lib "Altium Content Vault") (part "RES"))
    )
    (comp (ref "R42")
      (value "ERJ-3EKF3300V")
      (footprint "RESC1608X55X30LL15T15")
      (description "Chip Resistor, 330 Ohm, +/- 1%, 0.1 W, -55 to 155 degC, 0603 (1608 Metric), RoHS, Tape and Reel")
      (libsource (lib "Altium Content Vault") (part "RES-2"))
    )
    (comp (ref "R43")
      (value "ERJ-3EKF1200V")
      (footprint "RESC1609X55X30ML15T15")
      (description "Chip Resistor, 120 Ohm, +/- 1%, 0.1 W, -55 to 155 degC, 0603 (1608 Metric), RoHS, Tape and Reel")
      (fields (field (name "TOLERANCE") "1%") (field (name "MANUFACTURER") "Panasonic"))
      (libsource (lib "Altium Content Vault") (part "RES-2"))
    )
    (comp (ref "R44")
      (value "ERJ-3EKF3300V")
      (footprint "RESC1608X55X30LL15T15")
      (description "Chip Resistor, 330 Ohm, +/- 1%, 0.1 W, -55 to 155 degC, 0603 (1608 Metric), RoHS, Tape and Reel")
      (libsource (lib "Altium Content Vault") (part "RES-2"))
    )
    (comp (ref "R45")
      (value "ERJ3EKF1002V")
      (footprint "RESC1609X55X30LL15T15")
      (description "Chip Resistor, 10 KOhm, +/- 1%, 0.1 W, -55 to 155 degC, 0603 (1608 Metric), RoHS, Tape and Reel")
      (fields (field (name "TOLERANCE") "1%") (field (name "MANUFACTURER") "Panasonic"))
      (libsource (lib "Altium Content Vault") (part "RES-2"))
    )
    (comp (ref "R50")
      (value "ERJ3EKF1002V")
      (footprint "RESC1609X55X30LL15T15")
      (description "Chip Resistor, 10 KOhm, +/- 1%, 0.1 W, -55 to 155 degC, 0603 (1608 Metric), RoHS, Tape and Reel")
      (fields (field (name "TOLERANCE") "1%") (field (name "MANUFACTURER") "Panasonic"))
      (libsource (lib "Altium Content Vault") (part "RES-2"))
    )
    (comp (ref "R51")
      (value "ERJ3EKF1002V")
      (footprint "RESC1609X55X30LL15T15")
      (description "Chip Resistor, 10 KOhm, +/- 1%, 0.1 W, -55 to 155 degC, 0603 (1608 Metric), RoHS, Tape and Reel")
      (fields (field (name "TOLERANCE") "1%") (field (name "MANUFACTURER") "Panasonic"))
      (libsource (lib "Altium Content Vault") (part "RES-2"))
    )
    (comp (ref "R61")
      (value "ERJ3EKF1002V")
      (footprint "RESC1609X55X30LL15T15")
      (description "Chip Resistor, 10 KOhm, +/- 1%, 0.1 W, -55 to 155 degC, 0603 (1608 Metric), RoHS, Tape and Reel")
      (fields (field (name "TOLERANCE") "1%") (field (name "MANUFACTURER") "Panasonic"))
      (libsource (lib "Altium Content Vault") (part "RES-2"))
    )
    (comp (ref "R62")
      (value "ERJ3EKF56R0V")
      (footprint "RESC1608X55X30NL15T15")
      (fields (field (name "MANUFACTURER") "Panasonic"))
      (libsource (lib "Altium Content Vault") (part "RES"))
    )
    (comp (ref "R96")
      (value "ERJ-3EKF1001V")
      (footprint "RESC1608X55X30LL15T15")
      (fields (field (name "MANUFACTURER") "Panasonic"))
      (libsource (lib "Altium Content Vault") (part "RES"))
    )
    (comp (ref "R102")
      (value "ERJ-3EKF1001V")
      (footprint "RESC1608X55X30LL15T15")
      (fields (field (name "MANUFACTURER") "Panasonic"))
      (libsource (lib "Altium Content Vault") (part "RES"))
    )
    (comp (ref "SW1")
      (value "KXT331LHS")
      (footprint "FP-KXT331LHS-MFG")
      (description "SWITCH TACTILE SPST-NO 0.02A 15V")
      (libsource (lib "Altium Content Vault") (part "bb27bde45df87f1f469753f287ef5ae"))
    )
    (comp (ref "SW2")
      (value "KXT331LHS")
      (footprint "FP-KXT331LHS-MFG")
      (description "SWITCH TACTILE SPST-NO 0.02A 15V")
      (libsource (lib "Altium Content Vault") (part "bb27bde45df87f1f469753f287ef5ae"))
    )
    (comp (ref "SW3")
      (value "KXT331LHS")
      (footprint "FP-KXT331LHS-MFG")
      (description "SWITCH TACTILE SPST-NO 0.02A 15V")
      (libsource (lib "Altium Content Vault") (part "bb27bde45df87f1f469753f287ef5ae"))
    )
    (comp (ref "TP1")
      (value "TPAD6R")
      (footprint "TP06R")
      (description "0.6mm round")
      (libsource (lib "uORocketry Hardware") (part "CMP-001-0001-4"))
    )
    (comp (ref "TP2")
      (value "TPAD6R")
      (footprint "TP06R")
      (description "0.6mm round")
      (libsource (lib "uORocketry Hardware") (part "CMP-001-0001-4"))
    )
    (comp (ref "TP3")
      (value "TPAD6R")
      (footprint "TP06R")
      (description "0.6mm round")
      (libsource (lib "uORocketry Hardware") (part "CMP-001-0001-4"))
    )
    (comp (ref "TP4")
      (value "TPAD6R")
      (footprint "TP06R")
      (description "0.6mm round")
      (libsource (lib "uORocketry Hardware") (part "CMP-001-0001-4"))
    )
    (comp (ref "TP5")
      (value "TPAD6R")
      (footprint "TP06R")
      (description "0.6mm round")
      (libsource (lib "uORocketry Hardware") (part "CMP-001-0001-4"))
    )
    (comp (ref "TP6")
      (value "TPAD6R")
      (footprint "TP06R")
      (description "0.6mm round")
      (libsource (lib "uORocketry Hardware") (part "CMP-001-0001-4"))
    )
    (comp (ref "U1")
      (value "STM32H730VBT6")
      (footprint "FP-LQFP100-1L-IPC_C")
      (description "IC MCU 32BIT 128KB FLASH 100LQFP")
      (libsource (lib "Altium Content Vault") (part "44dc6501260a4d92b846760feb66c20"))
    )
    (comp (ref "U2")
      (value "ADC088S022CIMT/NOPB")
      (footprint "MTC16_L")
      (description "8-Channel, 50 kSPS to 200 kSPS, 8-Bit A/D Converter, 16-pin TSSOP, Pb-Free")
      (fields (field (name "MANUFACTURER") "National Semiconductor"))
      (libsource (lib "Altium Content Vault") (part "CON-ADC-ADC108S052CIMT"))
    )
    (comp (ref "U4")
      (value "TCAN1146DYYRQ1")
      (footprint "TCAN1146DYYRQ1-Footprint-1")
      (libsource (lib "uORocketry Hardware") (part "TCAN1146DYYRQ1"))
    )
    (comp (ref "U10")
      (value "AP7381-50Y-13")
      (footprint "FP-SOT89-MFG")
      (description "IC REG LINEAR 5V 150MA SOT89")
      (fields
        (field (name "MANUFACTURER") "Diodes Inc.")
        (field (name "OCTOPART") "https://octopart.com/ap7381-50y-13-diodes+inc.-87775116")
      )
      (libsource (lib "Altium Content Vault") (part "4c3da590f2d7b1882ad42f13e6d336b"))
    )
    (comp (ref "Y1")
      (value "ABM8-48.000MHZ-B2-T")
      (footprint "FP-ABM8-MFG")
      (description "Crystal 48MHz ±20ppm 18pF SMD-4 3.2mm x 2.5mm")
      (fields (field (name "TOLERANCE") "20ppm"))
      (libsource (lib "Altium Content Vault") (part "dfdb7f9a12507849fb681da9a70121c"))
    )
    (comp (ref "Y2")
      (value "ECS-.327-12.5-1210-TR")
      (footprint "FP-ECX-1210-MFG")
      (description "CRYSTAL 32.7680KHZ 12.5PF SMD")
      (fields
        (field (name "OCTOPART") "https://octopart.com/ecs-.327-12.5-1210-tr-ecs+international-81221340")
        (field (name "TOLERANCE") "20ppm")
      )
      (libsource (lib "Altium Content Vault") (part "99724985039315a44fd0d1401b84e49"))
    )
  )
  (nets
    (net (code "1") (name "/12V_INH") (class "Default")
      (node (ref "U1") (pin "62") (pinfunction "PD15_62") (pintype "bidirectional"))
    )
    (net (code "2") (name "/12V_SENSE") (class "Default")
      (node (ref "U2") (pin "4") (pinfunction "IN0_4") (pintype "input"))
    )
    (net (code "3") (name "/ADDR_1") (class "Default")
      (node (ref "U1") (pin "68") (pinfunction "PA9_68") (pintype "bidirectional"))
    )
    (net (code "4") (name "/ADDR_2") (class "Default")
      (node (ref "U1") (pin "67") (pinfunction "PA8_67") (pintype "bidirectional"))
    )
    (net (code "5") (name "/ADDR_3") (class "Default")
      (node (ref "U1") (pin "66") (pinfunction "PC9_66") (pintype "bidirectional"))
    )
    (net (code "6") (name "/ADDR_4") (class "Default")
      (node (ref "U1") (pin "65") (pinfunction "PC8_65") (pintype "bidirectional"))
    )
    (net (code "7") (name "/ADDR_5") (class "Default")
      (node (ref "U1") (pin "64") (pinfunction "PC7_64") (pintype "bidirectional"))
    )
    (net (code "8") (name "/ADDR_6") (class "Default")
      (node (ref "U1") (pin "63") (pinfunction "PC6_63") (pintype "bidirectional"))
    )
    (net (code "9") (name "/BOOT") (class "Default")
      (node (ref "C26") (pin "1") (pinfunction "1_1") (pintype "passive"))
      (node (ref "R19") (pin "1") (pinfunction "1_1") (pintype "passive"))
      (node (ref "R20") (pin "2") (pinfunction "2_2") (pintype "passive"))
      (node (ref "R25") (pin "2") (pinfunction "2_2") (pintype "passive"))
    )
    (net (code "10") (name "/BUZZ") (class "Default")
      (node (ref "R38") (pin "1") (pinfunction "1_1") (pintype "passive"))
      (node (ref "U1") (pin "61") (pinfunction "PD14_61") (pintype "bidirectional"))
    )
    (net (code "11") (name "/BUZZ_NEG") (class "Default")
      (node (ref "LS2") (pin "N") (pinfunction "N_N") (pintype "passive"))
      (node (ref "Q14") (pin "3") (pinfunction "Drain2_3") (pintype "passive"))
      (node (ref "Q14") (pin "6") (pinfunction "Drain1_6") (pintype "passive"))
      (node (ref "R40") (pin "1") (pinfunction "1_1") (pintype "passive"))
    )
    (net (code "12") (name "/CAN1_RX") (class "Default")
      (node (ref "R96") (pin "1") (pinfunction "1_1") (pintype "passive"))
      (node (ref "U1") (pin "81") (pinfunction "PD0_81") (pintype "bidirectional"))
      (node (ref "U4") (pin "4") (pinfunction "RXD_4") (pintype "output"))
    )
    (net (code "13") (name "/CAN1_TX") (class "Default")
      (node (ref "R102") (pin "1") (pinfunction "1_1") (pintype "passive"))
      (node (ref "U1") (pin "82") (pinfunction "PD1_82") (pintype "bidirectional"))
      (node (ref "U4") (pin "1") (pinfunction "TXD_1") (pintype "input"))
    )
    (net (code "14") (name "/CAN_INH") (class "Default")
      (node (ref "TP1") (pin "1") (pinfunction "TP_1") (pintype "passive"))
      (node (ref "U4") (pin "7") (pinfunction "INH/LIMP_7") (pintype "passive"))
    )
    (net (code "15") (name "/CAN_N") (class "Default")
      (node (ref "C33") (pin "1") (pinfunction "1_1") (pintype "passive"))
      (node (ref "D4") (pin "1") (pinfunction "1_1") (pintype "passive"))
      (node (ref "L2") (pin "4") (pinfunction "4_4") (pintype "passive"))
      (node (ref "R32") (pin "1") (pinfunction "1_1") (pintype "passive"))
      (node (ref "R43") (pin "1") (pinfunction "1_1") (pintype "passive"))
    )
    (net (code "16") (name "/CAN_P") (class "Default")
      (node (ref "C27") (pin "2") (pinfunction "2_2") (pintype "passive"))
      (node (ref "D4") (pin "2") (pinfunction "2_2") (pintype "passive"))
      (node (ref "L2") (pin "1") (pinfunction "1_1") (pintype "passive"))
      (node (ref "R30") (pin "2") (pinfunction "2_2") (pintype "passive"))
      (node (ref "R43") (pin "2") (pinfunction "2_2") (pintype "passive"))
    )
    (net (code "17") (name "/CAN_VSUP") (class "Default")
      (node (ref "D6") (pin "2") (pinfunction "A_2") (pintype "passive"))
    )
    (net (code "18") (name "/CAN_nCS") (class "Default")
      (node (ref "R26") (pin "2") (pinfunction "2_2") (pintype "passive"))
      (node (ref "U4") (pin "14") (pinfunction "nCS_14") (pintype "input"))
    )
    (net (code "19") (name "/DIAG_ADC_nCS") (class "Default")
      (node (ref "R28") (pin "1") (pinfunction "1_1") (pintype "passive"))
      (node (ref "U2") (pin "1") (pinfunction "~{CS}_1") (pintype "input"))
    )
    (net (code "20") (name "/G_LED") (class "Default")
      (node (ref "R34") (pin "1") (pinfunction "1_1") (pintype "passive"))
      (node (ref "U1") (pin "15") (pinfunction "PC0_15") (pintype "bidirectional"))
    )
    (net (code "21") (name "/INT_3V3_SENSE") (class "Default")
      (node (ref "U2") (pin "7") (pinfunction "IN3_7") (pintype "input"))
    )
    (net (code "22") (name "/INT_5V_SENSE") (class "Default")
      (node (ref "R50") (pin "1") (pinfunction "1_1") (pintype "passive"))
      (node (ref "R51") (pin "1") (pinfunction "1_1") (pintype "passive"))
      (node (ref "U2") (pin "6") (pinfunction "IN2_6") (pintype "input"))
    )
    (net (code "23") (name "/M1_TRIG") (class "Default")
      (node (ref "U1") (pin "32") (pinfunction "PC4_32") (pintype "bidirectional"))
    )
    (net (code "24") (name "/M2_TRIG") (class "Default")
      (node (ref "U1") (pin "34") (pinfunction "PB0_34") (pintype "bidirectional"))
    )
    (net (code "25") (name "/M3_TRIG") (class "Default")
      (node (ref "U1") (pin "35") (pinfunction "PB1_35") (pintype "bidirectional"))
    )
    (net (code "26") (name "/M4_TRIG") (class "Default")
      (node (ref "U1") (pin "37") (pinfunction "PE7_37") (pintype "bidirectional"))
    )
    (net (code "27") (name "/M5_TRIG") (class "Default")
      (node (ref "U1") (pin "38") (pinfunction "PE8_38") (pintype "bidirectional"))
    )
    (net (code "28") (name "/M6_TRIG") (class "Default")
      (node (ref "U1") (pin "40") (pinfunction "PE10_40") (pintype "bidirectional"))
    )
    (net (code "29") (name "/M7_TRIG") (class "Default")
      (node (ref "U1") (pin "45") (pinfunction "PE15_45") (pintype "bidirectional"))
    )
    (net (code "30") (name "/M8_TRIG") (class "Default")
      (node (ref "U1") (pin "47") (pinfunction "PB11_47") (pintype "bidirectional"))
    )
    (net (code "31") (name "/M9_TRIG") (class "Default")
      (node (ref "U1") (pin "55") (pinfunction "PD8_55") (pintype "bidirectional"))
    )
    (net (code "32") (name "/M10_TRIG") (class "Default")
      (node (ref "U1") (pin "57") (pinfunction "PD10_57") (pintype "bidirectional"))
    )
    (net (code "33") (name "/M11_TRIG") (class "Default")
      (node (ref "U1") (pin "58") (pinfunction "PD11_58") (pintype "bidirectional"))
    )
    (net (code "34") (name "/M12_STAT") (class "Default")
      (node (ref "U1") (pin "33") (pinfunction "PC5_33") (pintype "bidirectional"))
    )
    (net (code "35") (name "/M12_TRIG") (class "Default")
      (node (ref "U1") (pin "60") (pinfunction "PD13_60") (pintype "bidirectional"))
    )
    (net (code "36") (name "/M34_STAT") (class "Default")
      (node (ref "U1") (pin "36") (pinfunction "PB2_36") (pintype "bidirectional"))
    )
    (net (code "37") (name "/M56_STAT") (class "Default")
      (node (ref "U1") (pin "39") (pinfunction "PE9_39") (pintype "bidirectional"))
    )
    (net (code "38") (name "/M78_STAT") (class "Default")
      (node (ref "U1") (pin "46") (pinfunction "PB10_46") (pintype "bidirectional"))
    )
    (net (code "39") (name "/M910_STAT") (class "Default")
      (node (ref "U1") (pin "56") (pinfunction "PD9_56") (pintype "bidirectional"))
    )
    (net (code "40") (name "/M1112_STAT") (class "Default")
      (node (ref "U1") (pin "59") (pinfunction "PD12_59") (pintype "bidirectional"))
    )
    (net (code "41") (name "/M1234_TEMP") (class "Default")
      (node (ref "U2") (pin "9") (pinfunction "IN5_9") (pintype "input"))
    )
    (net (code "42") (name "/M5678_TEMP") (class "Default")
      (node (ref "U2") (pin "10") (pinfunction "IN6_10") (pintype "input"))
    )
    (net (code "43") (name "/M9101112_TEMP") (class "Default")
      (node (ref "U2") (pin "11") (pinfunction "IN7_11") (pintype "input"))
    )
    (net (code "44") (name "/PRE_12V_SENSE") (class "Default")
      (node (ref "U2") (pin "5") (pinfunction "IN1_5") (pintype "input"))
    )
    (net (code "45") (name "/PRE_CAN_N") (class "Default")
      (node (ref "L2") (pin "3") (pinfunction "3_3") (pintype "passive"))
      (node (ref "U4") (pin "12") (pinfunction "CANL_12") (pintype "bidirectional"))
    )
    (net (code "46") (name "/PRE_CAN_P") (class "Default")
      (node (ref "L2") (pin "2") (pinfunction "2_2") (pintype "passive"))
      (node (ref "U4") (pin "13") (pinfunction "CANH_13") (pintype "bidirectional"))
    )
    (net (code "48") (name "/RESETN") (class "Default")
      (node (ref "C17") (pin "1") (pinfunction "1_1") (pintype "passive"))
      (node (ref "J10") (pin "10") (pinfunction "nRESET_10") (pintype "input"))
      (node (ref "R24") (pin "2") (pinfunction "2_2") (pintype "passive"))
      (node (ref "R42") (pin "1") (pinfunction "1_1") (pintype "passive"))
      (node (ref "R45") (pin "2") (pinfunction "2_2") (pintype "passive"))
    )
    (net (code "49") (name "/R_LED") (class "Default")
      (node (ref "R39") (pin "1") (pinfunction "1_1") (pintype "passive"))
      (node (ref "U1") (pin "16") (pinfunction "PC1_16") (pintype "bidirectional"))
    )
    (net (code "50") (name "/SPI1_MISO") (class "Default")
      (node (ref "U1") (pin "30") (pinfunction "PA6_30") (pintype "bidirectional"))
    )
    (net (code "51") (name "/SPI1_MOSI") (class "Default")
      (node (ref "U1") (pin "31") (pinfunction "PA7_31") (pintype "bidirectional"))
    )
    (net (code "52") (name "/SPI1_SCLK") (class "Default")
      (node (ref "U1") (pin "29") (pinfunction "PA5_29") (pintype "bidirectional"))
    )
    (net (code "53") (name "/SPI1_nCS") (class "Default")
      (node (ref "U1") (pin "28") (pinfunction "PA4_28") (pintype "bidirectional"))
    )
    (net (code "54") (name "/SPI2_MISO") (class "Default")
      (node (ref "U1") (pin "53") (pinfunction "PB14_53") (pintype "bidirectional"))
    )
    (net (code "55") (name "/SPI2_MOSI") (class "Default")
      (node (ref "U1") (pin "54") (pinfunction "PB15_54") (pintype "bidirectional"))
    )
    (net (code "56") (name "/SPI2_SCLK") (class "Default")
      (node (ref "U1") (pin "52") (pinfunction "PB13_52") (pintype "bidirectional"))
    )
    (net (code "57") (name "/SPI2_nCS") (class "Default")
      (node (ref "U1") (pin "51") (pinfunction "PB12_51") (pintype "bidirectional"))
    )
    (net (code "58") (name "/SPI3_MISO") (class "Default")
      (node (ref "U1") (pin "79") (pinfunction "PC11_79") (pintype "bidirectional"))
      (node (ref "U2") (pin "15") (pinfunction "DOUT_15") (pintype "output"))
      (node (ref "U4") (pin "6") (pinfunction "nINT/SDO_6") (pintype "output"))
    )
    (net (code "59") (name "/SPI3_MOSI") (class "Default")
      (node (ref "U1") (pin "80") (pinfunction "PC12_80") (pintype "bidirectional"))
      (node (ref "U2") (pin "14") (pinfunction "DIN_14") (pintype "input"))
      (node (ref "U4") (pin "11") (pinfunction "SDI_11") (pintype "input"))
    )
    (net (code "60") (name "/SPI3_SCLK") (class "Default")
      (node (ref "U1") (pin "78") (pinfunction "PC10_78") (pintype "bidirectional"))
      (node (ref "U2") (pin "16") (pinfunction "SCLK_16") (pintype "input"))
      (node (ref "U4") (pin "8") (pinfunction "SCLK_8") (pintype "input"))
    )
    (net (code "61") (name "/SPI4_MISO") (class "Default")
      (node (ref "U1") (pin "43") (pinfunction "PE13_43") (pintype "bidirectional"))
    )
    (net (code "62") (name "/SPI4_MOSI") (class "Default")
      (node (ref "U1") (pin "44") (pinfunction "PE14_44") (pintype "bidirectional"))
    )
    (net (code "63") (name "/SPI4_SCLK") (class "Default")
      (node (ref "U1") (pin "42") (pinfunction "PE12_42") (pintype "bidirectional"))
    )
    (net (code "64") (name "/SPI4_nCS") (class "Default")
      (node (ref "U1") (pin "41") (pinfunction "PE11_41") (pintype "bidirectional"))
    )
    (net (code "65") (name "/SWCLK") (class "Default")
      (node (ref "J10") (pin "4") (pinfunction "SWCLK_4") (pintype "input"))
      (node (ref "R10") (pin "2") (pinfunction "2_2") (pintype "passive"))
      (node (ref "U1") (pin "76") (pinfunction "PA14_76") (pintype "bidirectional"))
    )
    (net (code "66") (name "/SWDIO") (class "Default")
      (node (ref "J10") (pin "2") (pinfunction "SWDIO_2") (pintype "input"))
      (node (ref "U1") (pin "72") (pinfunction "PA13_72") (pintype "bidirectional"))
    )
    (net (code "67") (name "/SWO") (class "Default")
      (node (ref "J10") (pin "6") (pinfunction "SWO_6") (pintype "input"))
      (node (ref "U1") (pin "89") (pinfunction "PB3_89") (pintype "bidirectional"))
    )
    (net (code "68") (name "/VCC_SENSE") (class "Default")
      (node (ref "U2") (pin "8") (pinfunction "IN4_8") (pintype "input"))
    )
    (net (code "69") (name "/VDDA") (class "Default")
      (node (ref "C11") (pin "2") (pinfunction "2_2") (pintype "passive"))
      (node (ref "C40") (pin "1") (pinfunction "1_1") (pintype "passive"))
      (node (ref "C7") (pin "1") (pinfunction "1_1") (pintype "passive"))
      (node (ref "C8") (pin "2") (pinfunction "2_2") (pintype "passive"))
      (node (ref "FB1") (pin "2") (pinfunction "2_2") (pintype "passive"))
      (node (ref "U1") (pin "20") (pinfunction "VREF+_20") (pintype "power_in"))
      (node (ref "U1") (pin "21") (pinfunction "VDDA_21") (pintype "power_in"))
    )
    (net (code "70") (name "/X32_N") (class "Default")
      (node (ref "C19") (pin "1") (pinfunction "1_1") (pintype "passive"))
      (node (ref "U1") (pin "9") (pinfunction "PC15-OSC32_OUT_9") (pintype "bidirectional"))
      (node (ref "Y2") (pin "2") (pinfunction "Out/In_2") (pintype "passive"))
    )
    (net (code "71") (name "/X32_P") (class "Default")
      (node (ref "C18") (pin "1") (pinfunction "1_1") (pintype "passive"))
      (node (ref "U1") (pin "8") (pinfunction "PC14-OSC32_IN_8") (pintype "bidirectional"))
      (node (ref "Y2") (pin "1") (pinfunction "In/Out_1") (pintype "passive"))
    )
    (net (code "72") (name "/X_N") (class "Default")
      (node (ref "C15") (pin "2") (pinfunction "2_2") (pintype "passive"))
      (node (ref "U1") (pin "13") (pinfunction "PH1-OSC_OUT_13") (pintype "bidirectional"))
      (node (ref "Y1") (pin "1") (pinfunction "1_1") (pintype "passive"))
    )
    (net (code "73") (name "/X_P") (class "Default")
      (node (ref "C14") (pin "2") (pinfunction "2_2") (pintype "passive"))
      (node (ref "U1") (pin "12") (pinfunction "PH0-OSC_IN_12") (pintype "bidirectional"))
      (node (ref "Y1") (pin "3") (pinfunction "3_3") (pintype "passive"))
    )
    (net (code "74") (name "3V3") (class "Default")
      (node (ref "C10") (pin "2") (pinfunction "2_2") (pintype "passive"))
      (node (ref "C12") (pin "1") (pinfunction "1_1") (pintype "passive"))
      (node (ref "C2") (pin "1") (pinfunction "1_1") (pintype "passive"))
      (node (ref "C26") (pin "2") (pinfunction "2_2") (pintype "passive"))
      (node (ref "C29") (pin "2") (pinfunction "2_2") (pintype "passive"))
      (node (ref "C3") (pin "2") (pinfunction "2_2") (pintype "passive"))
      (node (ref "C39") (pin "1") (pinfunction "1_1") (pintype "passive"))
      (node (ref "C4") (pin "2") (pinfunction "2_2") (pintype "passive"))
      (node (ref "C42") (pin "2") (pinfunction "2_2") (pintype "passive"))
      (node (ref "C5") (pin "2") (pinfunction "2_2") (pintype "passive"))
      (node (ref "C6") (pin "2") (pinfunction "2_2") (pintype "passive"))
      (node (ref "D7") (pin "2") (pinfunction "A_2") (pintype "passive"))
      (node (ref "D7") (pin "3") (pinfunction "A_3") (pintype "passive"))
      (node (ref "D9") (pin "2") (pinfunction "A_2") (pintype "passive"))
      (node (ref "D9") (pin "3") (pinfunction "A_3") (pintype "passive"))
      (node (ref "FB1") (pin "1") (pinfunction "1_1") (pintype "passive"))
      (node (ref "J10") (pin "1") (pinfunction "VTref_1") (pintype "input"))
      (node (ref "Q16") (pin "3") (pinfunction "D2_3") (pintype "passive"))
      (node (ref "Q16") (pin "6") (pinfunction "D1_6") (pintype "passive"))
      (node (ref "R10") (pin "1") (pinfunction "1_1") (pintype "passive"))
      (node (ref "R27") (pin "2") (pinfunction "2_2") (pintype "passive"))
      (node (ref "R36") (pin "2") (pinfunction "2_2") (pintype "passive"))
      (node (ref "R37") (pin "2") (pinfunction "2_2") (pintype "passive"))
      (node (ref "R45") (pin "1") (pinfunction "1_1") (pintype "passive"))
      (node (ref "R62") (pin "1") (pinfunction "1_1") (pintype "passive"))
      (node (ref "SW2") (pin "2") (pinfunction "2_2") (pintype "passive"))
      (node (ref "TP2") (pin "1") (pinfunction "TP_1") (pintype "passive"))
      (node (ref "U1") (pin "100") (pinfunction "VDD_100") (pintype "power_in"))
      (node (ref "U1") (pin "11") (pinfunction "VDD_11") (pintype "power_in"))
      (node (ref "U1") (pin "27") (pinfunction "VDD_27") (pintype "power_in"))
      (node (ref "U1") (pin "50") (pinfunction "VDD_50") (pintype "power_in"))
      (node (ref "U1") (pin "6") (pinfunction "VBAT_6") (pintype "power_in"))
      (node (ref "U1") (pin "75") (pinfunction "VDD_75") (pintype "power_in"))
      (node (ref "U2") (pin "2") (pinfunction "VA_2") (pintype "power_in"))
      (node (ref "U4") (pin "5") (pinfunction "VIO_5") (pintype "power_in"))
    )
    (net (code "75") (name "5V") (class "Default")
      (node (ref "C28") (pin "2") (pinfunction "2_2") (pintype "passive"))
      (node (ref "C34") (pin "2") (pinfunction "2_2") (pintype "passive"))
      (node (ref "R50") (pin "2") (pinfunction "2_2") (pintype "passive"))
      (node (ref "TP3") (pin "1") (pinfunction "TP_1") (pintype "passive"))
      (node (ref "U10") (pin "1") (pinfunction "VOUT_1") (pintype "power_in"))
      (node (ref "U4") (pin "3") (pinfunction "VCC_3") (pintype "power_in"))
    )
    (net (code "76") (name "GND") (class "Default")
      (node (ref "C1") (pin "2") (pinfunction "2_2") (pintype "passive"))
      (node (ref "C10") (pin "1") (pinfunction "1_1") (pintype "passive"))
      (node (ref "C11") (pin "1") (pinfunction "1_1") (pintype "passive"))
      (node (ref "C12") (pin "2") (pinfunction "2_2") (pintype "passive"))
      (node (ref "C13") (pin "2") (pinfunction "2_2") (pintype "passive"))
      (node (ref "C14") (pin "1") (pinfunction "1_1") (pintype "passive"))
      (node (ref "C15") (pin "1") (pinfunction "1_1") (pintype "passive"))
      (node (ref "C17") (pin "2") (pinfunction "2_2") (pintype "passive"))
      (node (ref "C18") (pin "2") (pinfunction "2_2") (pintype "passive"))
      (node (ref "C19") (pin "2") (pinfunction "2_2") (pintype "passive"))
      (node (ref "C2") (pin "2") (pinfunction "2_2") (pintype "passive"))
      (node (ref "C27") (pin "1") (pinfunction "1_1") (pintype "passive"))
      (node (ref "C28") (pin "1") (pinfunction "1_1") (pintype "passive"))
      (node (ref "C29") (pin "1") (pinfunction "1_1") (pintype "passive"))
      (node (ref "C3") (pin "1") (pinfunction "1_1") (pintype "passive"))
      (node (ref "C30") (pin "1") (pinfunction "1_1") (pintype "passive"))
      (node (ref "C31") (pin "1") (pinfunction "1_1") (pintype "passive"))
      (node (ref "C32") (pin "2") (pinfunction "2_2") (pintype "passive"))
      (node (ref "C33") (pin "2") (pinfunction "2_2") (pintype "passive"))
      (node (ref "C34") (pin "1") (pinfunction "1_1") (pintype "passive"))
      (node (ref "C35") (pin "1") (pinfunction "1_1") (pintype "passive"))
      (node (ref "C36") (pin "1") (pinfunction "1_1") (pintype "passive"))
      (node (ref "C37") (pin "1") (pinfunction "1_1") (pintype "passive"))
      (node (ref "C38") (pin "1") (pinfunction "1_1") (pintype "passive"))
      (node (ref "C39") (pin "2") (pinfunction "2_2") (pintype "passive"))
      (node (ref "C4") (pin "1") (pinfunction "1_1") (pintype "passive"))
      (node (ref "C40") (pin "2") (pinfunction "2_2") (pintype "passive"))
      (node (ref "C41") (pin "2") (pinfunction "2_2") (pintype "passive"))
      (node (ref "C42") (pin "1") (pinfunction "1_1") (pintype "passive"))
      (node (ref "C5") (pin "1") (pinfunction "1_1") (pintype "passive"))
      (node (ref "C6") (pin "1") (pinfunction "1_1") (pintype "passive"))
      (node (ref "C7") (pin "2") (pinfunction "2_2") (pintype "passive"))
      (node (ref "C8") (pin "1") (pinfunction "1_1") (pintype "passive"))
      (node (ref "C9") (pin "1") (pinfunction "1_1") (pintype "passive"))
      (node (ref "D4") (pin "3") (pinfunction "3_3") (pintype "passive"))
      (node (ref "J10") (pin "3") (pinfunction "GND_3") (pintype "input"))
      (node (ref "J10") (pin "5") (pinfunction "GND_5") (pintype "input"))
      (node (ref "Q14") (pin "1") (pinfunction "Source1_1") (pintype "passive"))
      (node (ref "Q14") (pin "4") (pinfunction "Source2_4") (pintype "passive"))
      (node (ref "R20") (pin "1") (pinfunction "1_1") (pintype "passive"))
      (node (ref "R33") (pin "1") (pinfunction "1_1") (pintype "passive"))
      (node (ref "R35") (pin "1") (pinfunction "1_1") (pintype "passive"))
      (node (ref "R44") (pin "2") (pinfunction "2_2") (pintype "passive"))
      (node (ref "R51") (pin "2") (pinfunction "2_2") (pintype "passive"))
      (node (ref "R61") (pin "1") (pinfunction "1_1") (pintype "passive"))
      (node (ref "SW1") (pin "2") (pinfunction "2_2") (pintype "passive"))
      (node (ref "SW3") (pin "1") (pinfunction "1_1") (pintype "passive"))
      (node (ref "TP4") (pin "1") (pinfunction "TP_1") (pintype "passive"))
      (node (ref "U1") (pin "10") (pinfunction "VSS_10") (pintype "power_in"))
      (node (ref "U1") (pin "19") (pinfunction "VSSA_19") (pintype "power_in"))
      (node (ref "U1") (pin "26") (pinfunction "VSS_26") (pintype "power_in"))
      (node (ref "U1") (pin "49") (pinfunction "VSS_49") (pintype "power_in"))
      (node (ref "U1") (pin "74") (pinfunction "VSS_74") (pintype "power_in"))
      (node (ref "U1") (pin "99") (pinfunction "VSS_99") (pintype "power_in"))
      (node (ref "U10") (pin "2") (pinfunction "GND_2") (pintype "power_in"))
      (node (ref "U2") (pin "12") (pinfunction "DGND_12") (pintype "power_in"))
      (node (ref "U2") (pin "3") (pinfunction "AGND_3") (pintype "power_in"))
      (node (ref "U4") (pin "2") (pinfunction "GND_2") (pintype "power_in"))
      (node (ref "Y1") (pin "2") (pinfunction "GND_2") (pintype "power_in"))
      (node (ref "Y1") (pin "4") (pinfunction "GND_4") (pintype "power_in"))
    )
    (net (code "77") (name "Net-(C31-Pad2)") (class "Default")
      (node (ref "C31") (pin "2") (pinfunction "2_2") (pintype "passive"))
      (node (ref "R29") (pin "2") (pinfunction "2_2") (pintype "passive"))
      (node (ref "R31") (pin "2") (pinfunction "2_2") (pintype "passive"))
      (node (ref "SW3") (pin "2") (pinfunction "2_2") (pintype "passive"))
    )
    (net (code "78") (name "Net-(C32-Pad1)") (class "Default")
      (node (ref "C32") (pin "1") (pinfunction "1_1") (pintype "passive"))
      (node (ref "R30") (pin "1") (pinfunction "1_1") (pintype "passive"))
      (node (ref "R32") (pin "2") (pinfunction "2_2") (pintype "passive"))
    )
    (net (code "79") (name "Net-(D6-C)") (class "Default")
      (node (ref "C30") (pin "2") (pinfunction "2_2") (pintype "passive"))
      (node (ref "D6") (pin "1") (pinfunction "C_1") (pintype "passive"))
      (node (ref "R29") (pin "1") (pinfunction "1_1") (pintype "passive"))
      (node (ref "U4") (pin "10") (pinfunction "VSUP_10") (pintype "power_in"))
    )
    (net (code "80") (name "Net-(D7-K-Pad1)") (class "Default")
      (node (ref "D7") (pin "1") (pinfunction "K_1") (pintype "passive"))
      (node (ref "R34") (pin "2") (pinfunction "2_2") (pintype "passive"))
    )
    (net (code "81") (name "Net-(D7-K-Pad4)") (class "Default")
      (node (ref "D7") (pin "4") (pinfunction "K_4") (pintype "passive"))
      (node (ref "R39") (pin "2") (pinfunction "2_2") (pintype "passive"))
    )
    (net (code "82") (name "Net-(D8-K-Pad1)") (class "Default")
      (node (ref "D8") (pin "1") (pinfunction "K_1") (pintype "passive"))
      (node (ref "R33") (pin "2") (pinfunction "2_2") (pintype "passive"))
    )
    (net (code "83") (name "Net-(D8-K-Pad4)") (class "Default")
      (node (ref "D8") (pin "4") (pinfunction "K_4") (pintype "passive"))
      (node (ref "R35") (pin "2") (pinfunction "2_2") (pintype "passive"))
    )
    (net (code "84") (name "Net-(D9-K-Pad1)") (class "Default")
      (node (ref "D9") (pin "1") (pinfunction "K_1") (pintype "passive"))
      (node (ref "R44") (pin "1") (pinfunction "1_1") (pintype "passive"))
    )
    (net (code "85") (name "Net-(D9-K-Pad4)") (class "Default")
      (node (ref "D9") (pin "4") (pinfunction "K_4") (pintype "passive"))
      (node (ref "R40") (pin "2") (pinfunction "2_2") (pintype "passive"))
    )
    (net (code "86") (name "Net-(Q14A-Gate1)") (class "Default")
      (node (ref "Q14") (pin "2") (pinfunction "Gate1_2") (pintype "passive"))
      (node (ref "Q14") (pin "5") (pinfunction "Gate2_5") (pintype "passive"))
      (node (ref "R36") (pin "1") (pinfunction "1_1") (pintype "passive"))
      (node (ref "R38") (pin "2") (pinfunction "2_2") (pintype "passive"))
    )
    (net (code "87") (name "Net-(Q16A-G1)") (class "Default")
      (node (ref "Q16") (pin "2") (pinfunction "G1_2") (pintype "passive"))
      (node (ref "R27") (pin "1") (pinfunction "1_1") (pintype "passive"))
      (node (ref "R96") (pin "2") (pinfunction "2_2") (pintype "passive"))
    )
    (net (code "88") (name "Net-(Q16A-S1)") (class "Default")
      (node (ref "D8") (pin "2") (pinfunction "A_2") (pintype "passive"))
      (node (ref "Q16") (pin "1") (pinfunction "S1_1") (pintype "passive"))
    )
    (net (code "89") (name "Net-(Q16B-G2)") (class "Default")
      (node (ref "Q16") (pin "5") (pinfunction "G2_5") (pintype "passive"))
      (node (ref "R102") (pin "2") (pinfunction "2_2") (pintype "passive"))
      (node (ref "R37") (pin "1") (pinfunction "1_1") (pintype "passive"))
    )
    (net (code "90") (name "Net-(Q16B-S2)") (class "Default")
      (node (ref "D8") (pin "3") (pinfunction "A_3") (pintype "passive"))
      (node (ref "Q16") (pin "4") (pinfunction "S2_4") (pintype "passive"))
    )
    (net (code "91") (name "Net-(R19-Pad2)") (class "Default")
      (node (ref "R19") (pin "2") (pinfunction "2_2") (pintype "passive"))
      (node (ref "SW2") (pin "1") (pinfunction "1_1") (pintype "passive"))
    )
    (net (code "92") (name "Net-(R42-Pad2)") (class "Default")
      (node (ref "R42") (pin "2") (pinfunction "2_2") (pintype "passive"))
      (node (ref "SW1") (pin "1") (pinfunction "1_1") (pintype "passive"))
    )
    (net (code "93") (name "Net-(TP5-TP)") (class "Default")
      (node (ref "C36") (pin "2") (pinfunction "2_2") (pintype "passive"))
      (node (ref "C37") (pin "2") (pinfunction "2_2") (pintype "passive"))
      (node (ref "TP5") (pin "1") (pinfunction "TP_1") (pintype "passive"))
      (node (ref "U1") (pin "48") (pinfunction "VCAP_48") (pintype "power_in"))
    )
    (net (code "94") (name "Net-(TP6-TP)") (class "Default")
      (node (ref "C38") (pin "2") (pinfunction "2_2") (pintype "passive"))
      (node (ref "C9") (pin "2") (pinfunction "2_2") (pintype "passive"))
      (node (ref "TP6") (pin "1") (pinfunction "TP_1") (pintype "passive"))
      (node (ref "U1") (pin "73") (pinfunction "VCAP_73") (pintype "power_in"))
    )
    (net (code "95") (name "Net-(U1B-BOOT0)") (class "Default")
      (node (ref "R25") (pin "1") (pinfunction "1_1") (pintype "passive"))
      (node (ref "R61") (pin "2") (pinfunction "2_2") (pintype "passive"))
      (node (ref "U1") (pin "94") (pinfunction "BOOT0_94") (pintype "input"))
    )
    (net (code "96") (name "Net-(U1B-PA15)") (class "Default")
      (node (ref "R28") (pin "2") (pinfunction "2_2") (pintype "passive"))
      (node (ref "U1") (pin "77") (pinfunction "PA15_77") (pintype "bidirectional"))
    )
    (net (code "97") (name "Net-(U1B-PD4)") (class "Default")
      (node (ref "R26") (pin "1") (pinfunction "1_1") (pintype "passive"))
      (node (ref "U1") (pin "85") (pinfunction "PD4_85") (pintype "bidirectional"))
    )
    (net (code "98") (name "Net-(U1B-~{RST})") (class "Default")
      (node (ref "C1") (pin "1") (pinfunction "1_1") (pintype "passive"))
      (node (ref "R24") (pin "1") (pinfunction "1_1") (pintype "passive"))
      (node (ref "U1") (pin "14") (pinfunction "~{RST}_14") (pintype "input"))
    )
    (net (code "99") (name "Net-(U2-VD)") (class "Default")
      (node (ref "C13") (pin "1") (pinfunction "1_1") (pintype "passive"))
      (node (ref "C41") (pin "1") (pinfunction "1_1") (pintype "passive"))
      (node (ref "R62") (pin "2") (pinfunction "2_2") (pintype "passive"))
      (node (ref "U2") (pin "13") (pinfunction "VD_13") (pintype "power_in"))
    )
    (net (code "100") (name "Net-(U4-WAKE)") (class "Default")
      (node (ref "R31") (pin "1") (pinfunction "1_1") (pintype "passive"))
      (node (ref "U4") (pin "9") (pinfunction "WAKE_9") (pintype "input"))
    )
    (net (code "101") (name "VCC") (class "Default")
      (node (ref "C35") (pin "2") (pinfunction "2_2") (pintype "passive"))
      (node (ref "LS2") (pin "P") (pinfunction "P_P") (pintype "passive"))
      (node (ref "U10") (pin "3") (pinfunction "VIN_3") (pintype "power_in"))
    )
    (net (code "102") (name "unconnected-(J10-NC-Pad7)") (class "Default")
      (node (ref "J10") (pin "7") (pinfunction "NC_7") (pintype "input+no_connect"))
    )
    (net (code "103") (name "unconnected-(J10-NC-Pad9)") (class "Default")
      (node (ref "J10") (pin "9") (pinfunction "NC_9") (pintype "input+no_connect"))
    )
    (net (code "104") (name "unconnected-(J10-TDI-Pad8)") (class "Default")
      (node (ref "J10") (pin "8") (pinfunction "TDI_8") (pintype "input+no_connect"))
    )
    (net (code "105") (name "unconnected-(U1B-PA0-Pad22)") (class "Default")
      (node (ref "U1") (pin "22") (pinfunction "PA0_22") (pintype "bidirectional"))
    )
    (net (code "106") (name "unconnected-(U1B-PA1-Pad23)") (class "Default")
      (node (ref "U1") (pin "23") (pinfunction "PA1_23") (pintype "bidirectional"))
    )
    (net (code "107") (name "unconnected-(U1B-PA2-Pad24)") (class "Default")
      (node (ref "U1") (pin "24") (pinfunction "PA2_24") (pintype "bidirectional"))
    )
    (net (code "108") (name "unconnected-(U1B-PA3-Pad25)") (class "Default")
      (node (ref "U1") (pin "25") (pinfunction "PA3_25") (pintype "bidirectional"))
    )
    (net (code "109") (name "unconnected-(U1B-PA10-Pad69)") (class "Default")
      (node (ref "U1") (pin "69") (pinfunction "PA10_69") (pintype "bidirectional"))
    )
    (net (code "110") (name "unconnected-(U1B-PA11-Pad70)") (class "Default")
      (node (ref "U1") (pin "70") (pinfunction "PA11_70") (pintype "bidirectional"))
    )
    (net (code "111") (name "unconnected-(U1B-PA12-Pad71)") (class "Default")
      (node (ref "U1") (pin "71") (pinfunction "PA12_71") (pintype "bidirectional"))
    )
    (net (code "112") (name "unconnected-(U1B-PB4-Pad90)") (class "Default")
      (node (ref "U1") (pin "90") (pinfunction "PB4_90") (pintype "bidirectional"))
    )
    (net (code "113") (name "unconnected-(U1B-PB5-Pad91)") (class "Default")
      (node (ref "U1") (pin "91") (pinfunction "PB5_91") (pintype "bidirectional"))
    )
    (net (code "114") (name "unconnected-(U1B-PB6-Pad92)") (class "Default")
      (node (ref "U1") (pin "92") (pinfunction "PB6_92") (pintype "bidirectional"))
    )
    (net (code "115") (name "unconnected-(U1B-PB7-Pad93)") (class "Default")
      (node (ref "U1") (pin "93") (pinfunction "PB7_93") (pintype "bidirectional"))
    )
    (net (code "116") (name "unconnected-(U1B-PB8-Pad95)") (class "Default")
      (node (ref "U1") (pin "95") (pinfunction "PB8_95") (pintype "bidirectional"))
    )
    (net (code "117") (name "unconnected-(U1B-PB9-Pad96)") (class "Default")
      (node (ref "U1") (pin "96") (pinfunction "PB9_96") (pintype "bidirectional"))
    )
    (net (code "118") (name "unconnected-(U1B-PC2_C-Pad17)") (class "Default")
      (node (ref "U1") (pin "17") (pinfunction "PC2_C_17") (pintype "bidirectional"))
    )
    (net (code "119") (name "unconnected-(U1B-PC3_C-Pad18)") (class "Default")
      (node (ref "U1") (pin "18") (pinfunction "PC3_C_18") (pintype "bidirectional"))
    )
    (net (code "120") (name "unconnected-(U1B-PC13-Pad7)") (class "Default")
      (node (ref "U1") (pin "7") (pinfunction "PC13_7") (pintype "bidirectional"))
    )
    (net (code "121") (name "unconnected-(U1B-PD2-Pad83)") (class "Default")
      (node (ref "U1") (pin "83") (pinfunction "PD2_83") (pintype "bidirectional"))
    )
    (net (code "122") (name "unconnected-(U1B-PD3-Pad84)") (class "Default")
      (node (ref "U1") (pin "84") (pinfunction "PD3_84") (pintype "bidirectional"))
    )
    (net (code "123") (name "unconnected-(U1B-PD5-Pad86)") (class "Default")
      (node (ref "U1") (pin "86") (pinfunction "PD5_86") (pintype "bidirectional"))
    )
    (net (code "124") (name "unconnected-(U1B-PD6-Pad87)") (class "Default")
      (node (ref "U1") (pin "87") (pinfunction "PD6_87") (pintype "bidirectional"))
    )
    (net (code "125") (name "unconnected-(U1B-PD7-Pad88)") (class "Default")
      (node (ref "U1") (pin "88") (pinfunction "PD7_88") (pintype "bidirectional"))
    )
    (net (code "126") (name "unconnected-(U1B-PE0-Pad97)") (class "Default")
      (node (ref "U1") (pin "97") (pinfunction "PE0_97") (pintype "bidirectional"))
    )
    (net (code "127") (name "unconnected-(U1B-PE1-Pad98)") (class "Default")
      (node (ref "U1") (pin "98") (pinfunction "PE1_98") (pintype "bidirectional"))
    )
    (net (code "128") (name "unconnected-(U1B-PE2-Pad1)") (class "Default")
      (node (ref "U1") (pin "1") (pinfunction "PE2_1") (pintype "bidirectional"))
    )
    (net (code "129") (name "unconnected-(U1B-PE3-Pad2)") (class "Default")
      (node (ref "U1") (pin "2") (pinfunction "PE3_2") (pintype "bidirectional"))
    )
    (net (code "130") (name "unconnected-(U1B-PE4-Pad3)") (class "Default")
      (node (ref "U1") (pin "3") (pinfunction "PE4_3") (pintype "bidirectional"))
    )
    (net (code "131") (name "unconnected-(U1B-PE5-Pad4)") (class "Default")
      (node (ref "U1") (pin "4") (pinfunction "PE5_4") (pintype "bidirectional"))
    )
    (net (code "132") (name "unconnected-(U1B-PE6-Pad5)") (class "Default")
      (node (ref "U1") (pin "5") (pinfunction "PE6_5") (pintype "bidirectional"))
    )
  )
)
